# EEZ_CF-DIC_r5B7.net
KiCad netlist of a schematic drawn in EAGLE
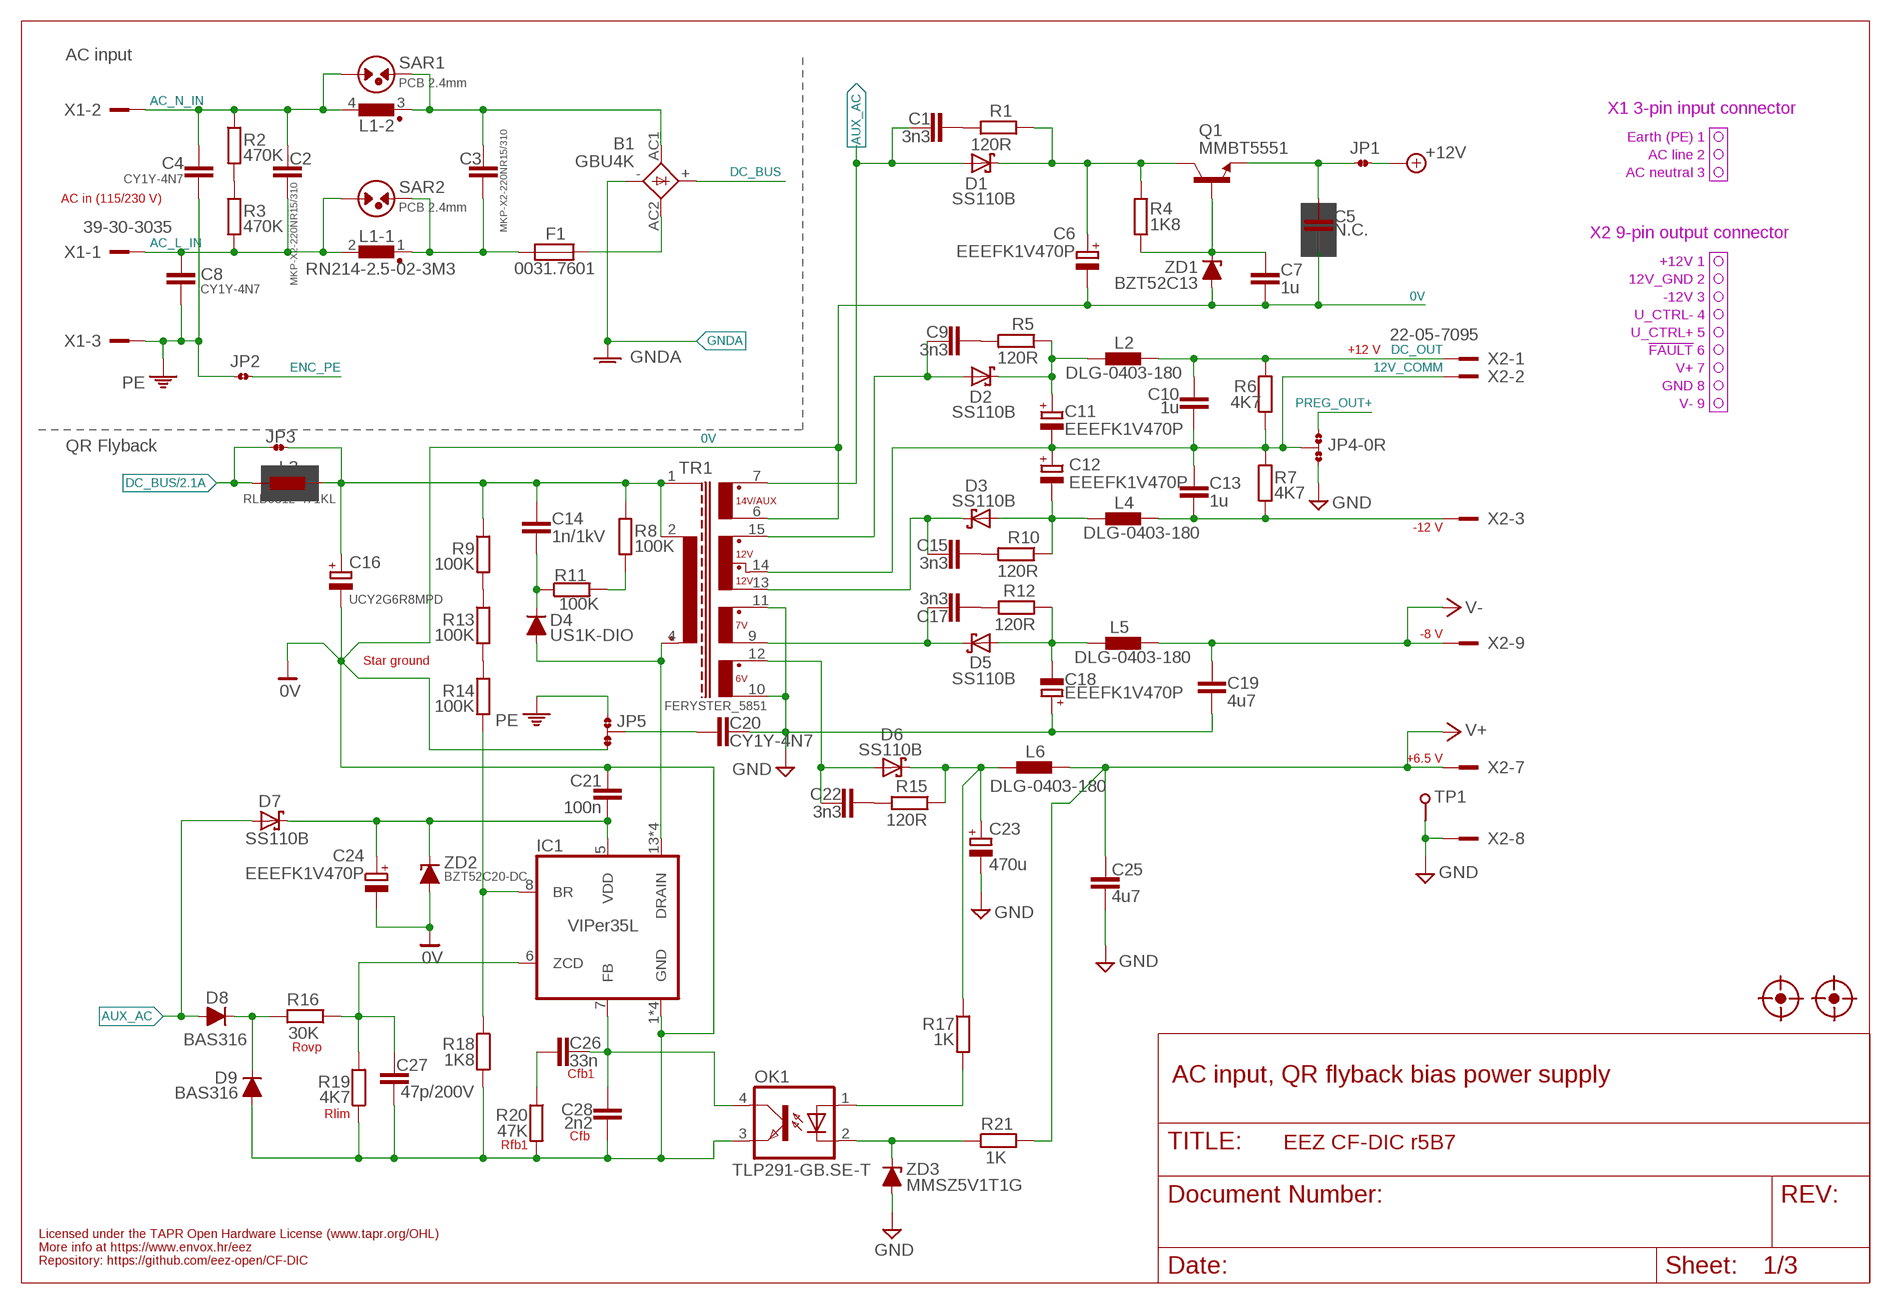
[diagram p0: schematic, sheet 1]
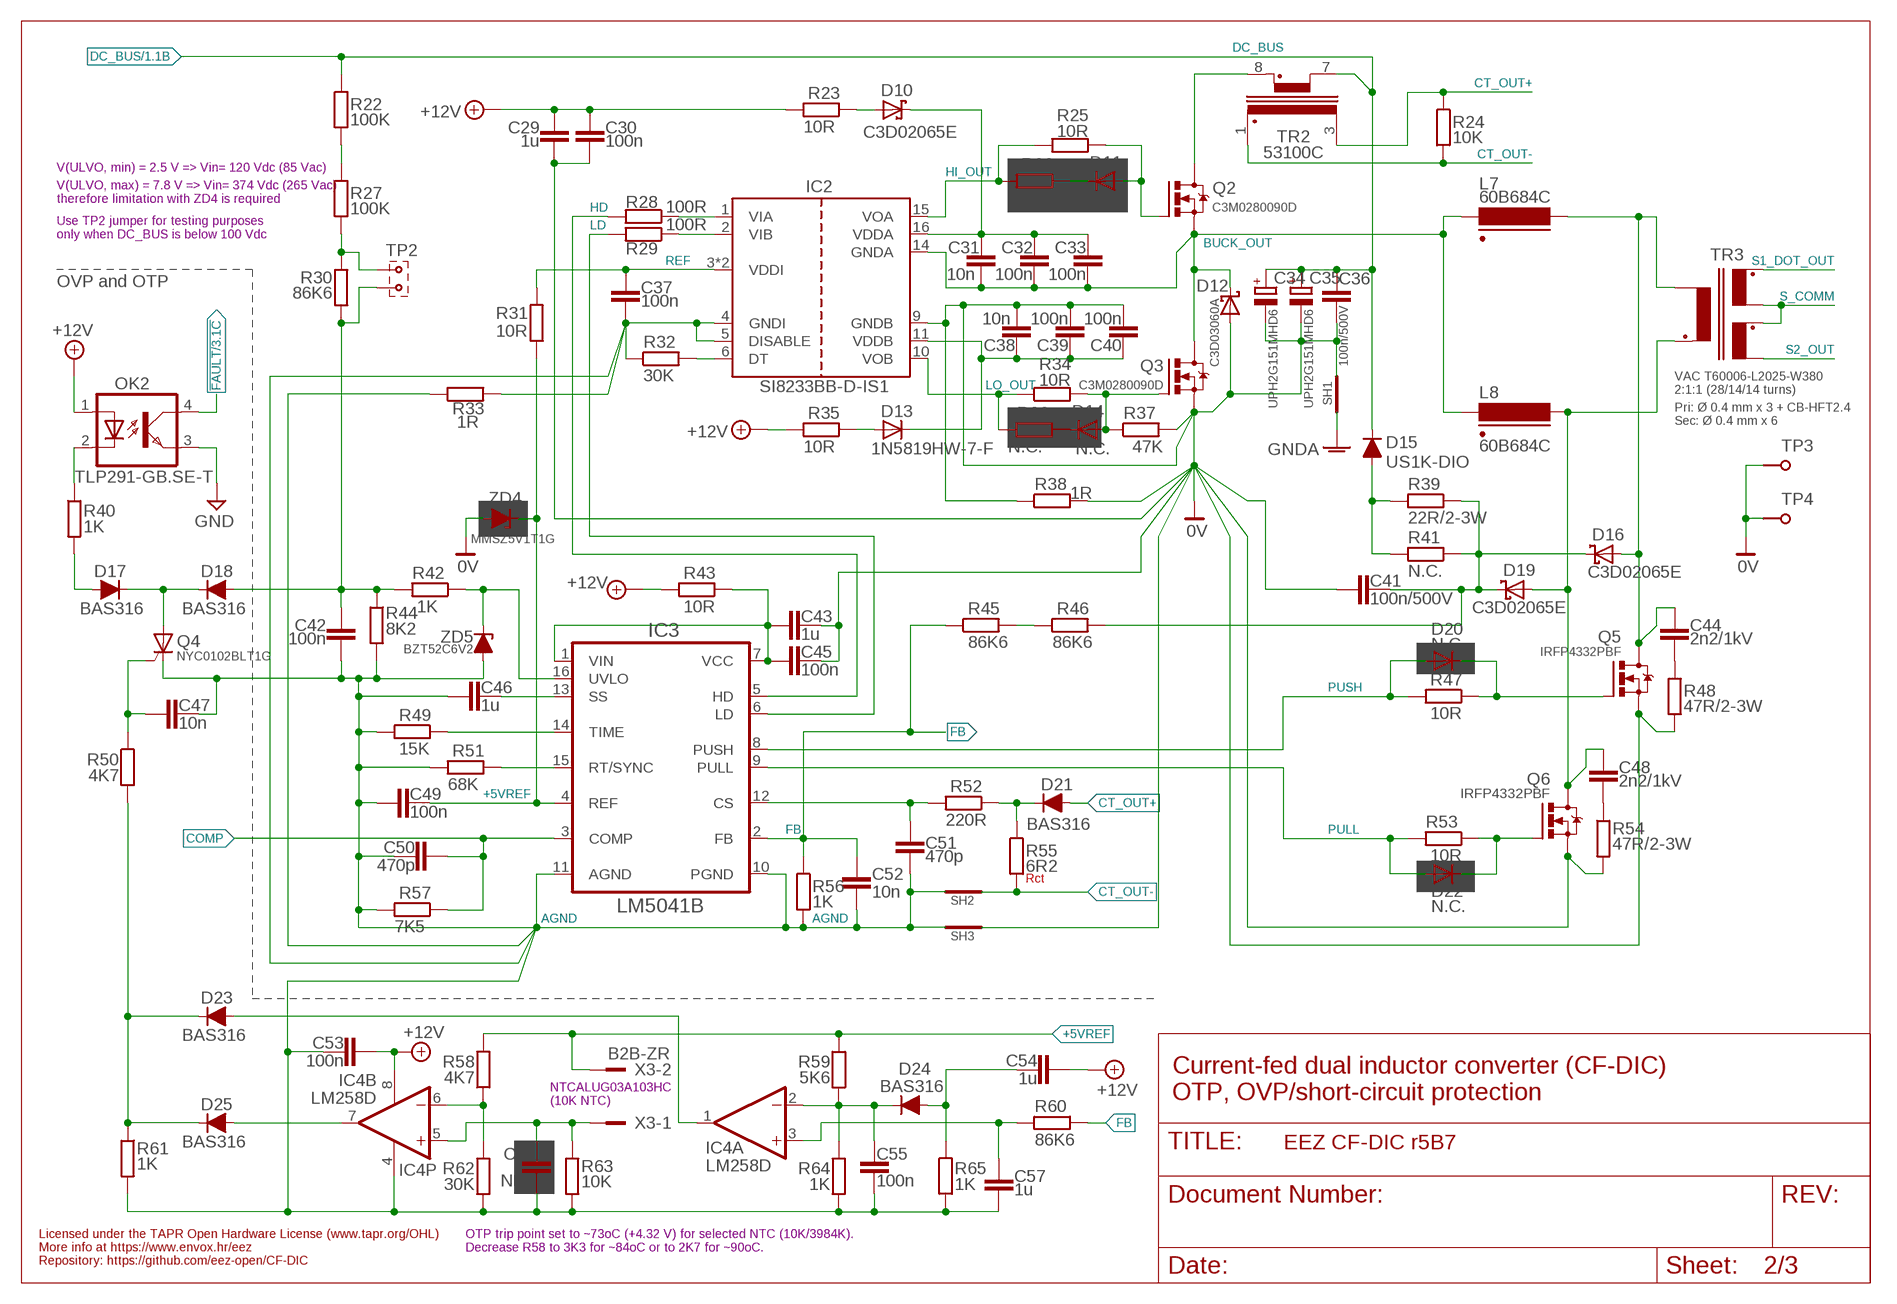
[diagram p1: schematic, sheet 2]
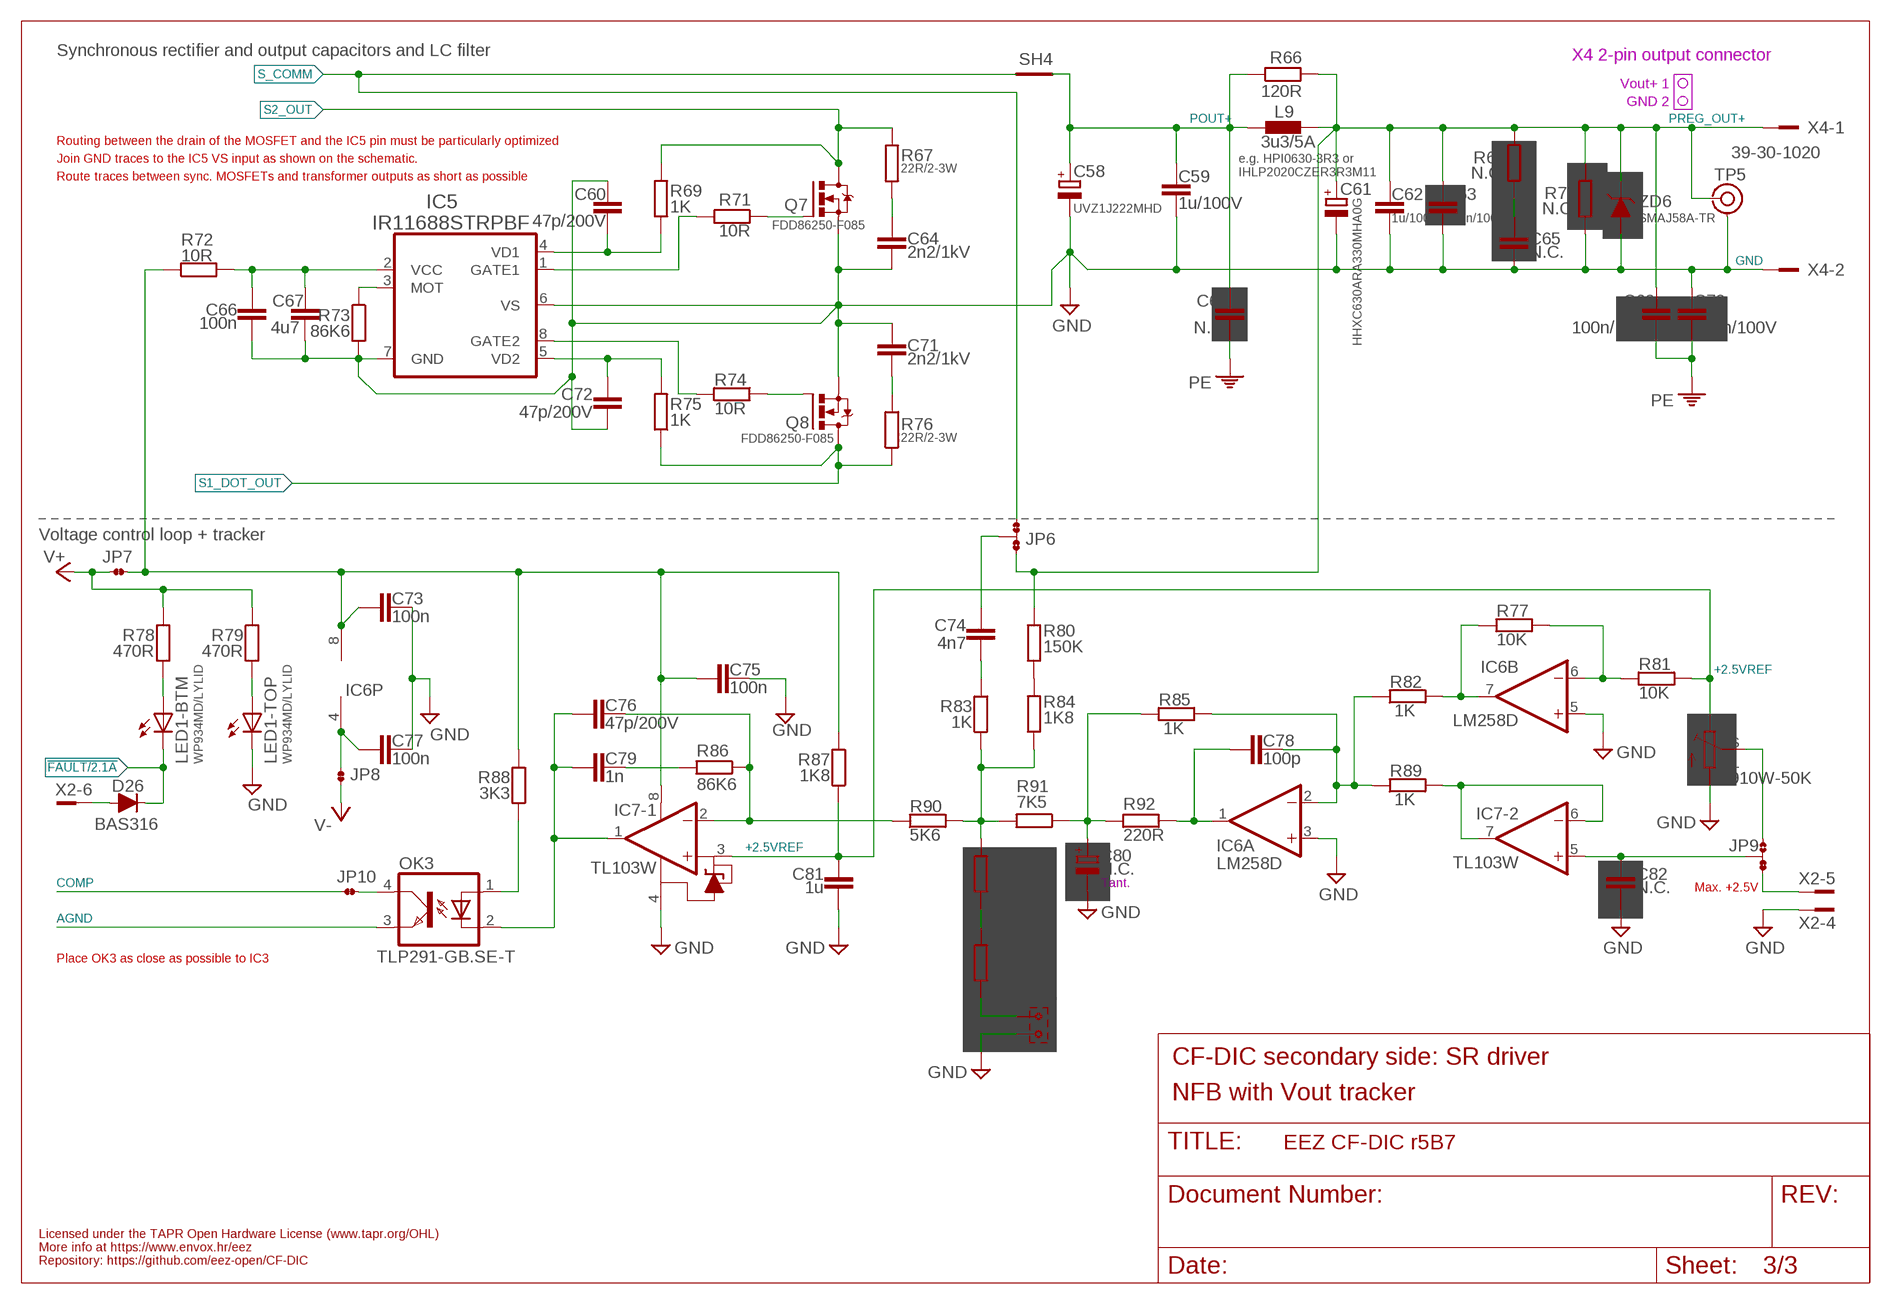
[diagram p2: schematic, sheet 3]

(export (version "E")
  (design (tool "Eeschema 10.0.6"))
  (components
    (comp (ref "C58")
      (value "UVZ1J222MHD")
      (footprint "eagle-import:ECAP7.5_18-H35.5A")
      (libsource (lib "eagle-import") (part "ECAPH35.5A"))
    )
    (comp (ref "C59")
      (value "1u/100V")
      (footprint "eagle-import:C1206")
      (libsource (lib "eagle-import") (part "C-EUC1206"))
    )
    (comp (ref "C60")
      (value "47p/200V")
      (footprint "eagle-import:C0805")
      (libsource (lib "eagle-import") (part "C-EUC0805"))
    )
    (comp (ref "C61")
      (value "HHXC630ARA330MHA0G")
      (footprint "eagle-import:CAPAE830X1050N")
      (libsource (lib "eagle-import") (part "ECAPSMD8.3MM/HA0"))
    )
    (comp (ref "C62")
      (value "1u/100V")
      (footprint "eagle-import:C1206")
      (libsource (lib "eagle-import") (part "C-EUC1206"))
    )
    (comp (ref "C63")
      (value "100n/100V")
      (footprint "eagle-import:C1206")
      (libsource (lib "eagle-import") (part "C-EUC1206"))
    )
    (comp (ref "C64")
      (value "2n2/1kV")
      (footprint "eagle-import:C1210")
      (libsource (lib "eagle-import") (part "C-EUC1210"))
    )
    (comp (ref "C65")
      (value "N.C.")
      (footprint "eagle-import:C1206")
      (libsource (lib "eagle-import") (part "C-EUC1206"))
    )
    (comp (ref "C66")
      (value "100n")
      (footprint "eagle-import:C0603")
      (libsource (lib "eagle-import") (part "C-EUC0603"))
    )
    (comp (ref "C67")
      (value "4u7")
      (footprint "eagle-import:C1206")
      (libsource (lib "eagle-import") (part "C-EUC1206"))
    )
    (comp (ref "C68")
      (value "N.C.")
      (footprint "eagle-import:C1206")
      (libsource (lib "eagle-import") (part "C-EUC1206"))
    )
    (comp (ref "C69")
      (value "100n/100V")
      (footprint "eagle-import:C1206")
      (libsource (lib "eagle-import") (part "C-EUC1206"))
    )
    (comp (ref "C70")
      (value "100n/100V")
      (footprint "eagle-import:C1206")
      (libsource (lib "eagle-import") (part "C-EUC1206"))
    )
    (comp (ref "C71")
      (value "2n2/1kV")
      (footprint "eagle-import:C1210")
      (libsource (lib "eagle-import") (part "C-EUC1210"))
    )
    (comp (ref "C72")
      (value "47p/200V")
      (footprint "eagle-import:C0805")
      (libsource (lib "eagle-import") (part "C-EUC0805"))
    )
    (comp (ref "C73")
      (value "100n")
      (footprint "eagle-import:C0603")
      (libsource (lib "eagle-import") (part "C-EUC0603"))
    )
    (comp (ref "C74")
      (value "4n7")
      (footprint "eagle-import:C0805")
      (libsource (lib "eagle-import") (part "C-EUC0805"))
    )
    (comp (ref "C75")
      (value "100n")
      (footprint "eagle-import:C0603")
      (libsource (lib "eagle-import") (part "C-EUC0603"))
    )
    (comp (ref "C76")
      (value "47p/200V")
      (footprint "eagle-import:C0805")
      (libsource (lib "eagle-import") (part "C-EUC0805"))
    )
    (comp (ref "C77")
      (value "100n")
      (footprint "eagle-import:C0603")
      (libsource (lib "eagle-import") (part "C-EUC0603"))
    )
    (comp (ref "C78")
      (value "100p")
      (footprint "eagle-import:C0805")
      (libsource (lib "eagle-import") (part "C-EUC0805"))
    )
    (comp (ref "C79")
      (value "1n")
      (footprint "eagle-import:C0805")
      (libsource (lib "eagle-import") (part "C-EUC0805"))
    )
    (comp (ref "C80")
      (value "N.C.")
      (footprint "eagle-import:EC1206")
      (libsource (lib "eagle-import") (part "ECAP1206"))
    )
    (comp (ref "C81")
      (value "1u")
      (footprint "eagle-import:C0805")
      (libsource (lib "eagle-import") (part "C-EUC0805"))
    )
    (comp (ref "C82")
      (value "N.C.")
      (footprint "eagle-import:C0805")
      (libsource (lib "eagle-import") (part "C-EUC0805"))
    )
    (comp (ref "D26")
      (value "BAS316")
      (footprint "eagle-import:SOD323-R")
      (libsource (lib "eagle-import") (part "DIODESOD323R"))
    )
    (comp (ref "IC5")
      (value "IR11688STRPBF")
      (footprint "eagle-import:SO8")
      (libsource (lib "eagle-import") (part "IR11688"))
    )
    (comp (ref "IC6")
      (value "LM258D")
      (footprint "eagle-import:SOIC127P600X173-8N")
      (libsource (lib "eagle-import") (part "TL072SOIC8"))
    )
    (comp (ref "IC7")
      (value "TL103W")
      (footprint "eagle-import:SOIC127P600X173-8N")
      (libsource (lib "eagle-import") (part "TL103W"))
    )
    (comp (ref "JP6")
      (value "JP3-CUT")
      (footprint "eagle-import:JP3-CUT")
      (libsource (lib "eagle-import") (part "JP3-CUT"))
    )
    (comp (ref "JP7")
      (value "JP2-NOCUT")
      (footprint "eagle-import:JP2-NOCUT")
      (libsource (lib "eagle-import") (part "JP2-NOCUT"))
    )
    (comp (ref "JP8")
      (value "JP2-NOCUT")
      (footprint "eagle-import:JP2-NOCUT")
      (libsource (lib "eagle-import") (part "JP2-NOCUT"))
    )
    (comp (ref "JP9")
      (value "JP3-CUT")
      (footprint "eagle-import:JP3-CUT")
      (libsource (lib "eagle-import") (part "JP3-CUT"))
    )
    (comp (ref "JP10")
      (value "JP2-NOCUT")
      (footprint "eagle-import:JP2-NOCUT")
      (libsource (lib "eagle-import") (part "JP2-NOCUT"))
    )
    (comp (ref "L9")
      (value "3u3/5A")
      (footprint "eagle-import:COILCRAFT_HPI0630")
      (libsource (lib "eagle-import") (part "COILCRAFT_HPI0630"))
    )
    (comp (ref "LED1")
      (value "WP934MD/LYLID")
      (footprint "eagle-import:WP934MD")
      (libsource (lib "eagle-import") (part "WP934MD/LYLID"))
    )
    (comp (ref "OK3")
      (value "TLP291-GB.SE-T")
      (footprint "eagle-import:SO4")
      (libsource (lib "eagle-import") (part "TLP291"))
    )
    (comp (ref "P1")
      (value "T910W-50K")
      (footprint "eagle-import:S64W")
      (libsource (lib "eagle-import") (part "TPOT-S64W"))
    )
    (comp (ref "Q7")
      (value "FDD86250-F085")
      (footprint "eagle-import:TO229P990X239-3N")
      (libsource (lib "eagle-import") (part "N-MOSFETDPAK"))
    )
    (comp (ref "Q8")
      (value "FDD86250-F085")
      (footprint "eagle-import:TO229P990X239-3N")
      (libsource (lib "eagle-import") (part "N-MOSFETDPAK"))
    )
    (comp (ref "R66")
      (value "120R")
      (footprint "eagle-import:R0805")
      (libsource (lib "eagle-import") (part "R-EU_R0805"))
    )
    (comp (ref "R67")
      (value "22R/2-3W")
      (footprint "eagle-import:R2512")
      (libsource (lib "eagle-import") (part "R-EU_R2512"))
    )
    (comp (ref "R68")
      (value "N.C.")
      (footprint "eagle-import:R1210")
      (libsource (lib "eagle-import") (part "R-EU_R1210"))
    )
    (comp (ref "R69")
      (value "1K")
      (footprint "eagle-import:R0805")
      (libsource (lib "eagle-import") (part "R-EU_R0805"))
    )
    (comp (ref "R70")
      (value "N.C.")
      (footprint "eagle-import:R2512")
      (libsource (lib "eagle-import") (part "R-EU_R2512"))
    )
    (comp (ref "R71")
      (value "10R")
      (footprint "eagle-import:R0805")
      (libsource (lib "eagle-import") (part "R-EU_R0805"))
    )
    (comp (ref "R72")
      (value "10R")
      (footprint "eagle-import:R0805")
      (libsource (lib "eagle-import") (part "R-EU_R0805"))
    )
    (comp (ref "R73")
      (value "86K6")
      (footprint "eagle-import:R0805")
      (libsource (lib "eagle-import") (part "R-EU_R0805"))
    )
    (comp (ref "R74")
      (value "10R")
      (footprint "eagle-import:R0805")
      (libsource (lib "eagle-import") (part "R-EU_R0805"))
    )
    (comp (ref "R75")
      (value "1K")
      (footprint "eagle-import:R0805")
      (libsource (lib "eagle-import") (part "R-EU_R0805"))
    )
    (comp (ref "R76")
      (value "22R/2-3W")
      (footprint "eagle-import:R2512")
      (libsource (lib "eagle-import") (part "R-EU_R2512"))
    )
    (comp (ref "R77")
      (value "10K")
      (footprint "eagle-import:R0805")
      (libsource (lib "eagle-import") (part "R-EU_R0805"))
    )
    (comp (ref "R78")
      (value "470R")
      (footprint "eagle-import:R0805")
      (libsource (lib "eagle-import") (part "R-EU_R0805"))
    )
    (comp (ref "R79")
      (value "470R")
      (footprint "eagle-import:R0805")
      (libsource (lib "eagle-import") (part "R-EU_R0805"))
    )
    (comp (ref "R80")
      (value "150K")
      (footprint "eagle-import:R0805")
      (libsource (lib "eagle-import") (part "R-EU_R0805"))
    )
    (comp (ref "R81")
      (value "10K")
      (footprint "eagle-import:R0805")
      (libsource (lib "eagle-import") (part "R-EU_R0805"))
    )
    (comp (ref "R82")
      (value "1K")
      (footprint "eagle-import:R0805")
      (libsource (lib "eagle-import") (part "R-EU_R0805"))
    )
    (comp (ref "R83")
      (value "1K")
      (footprint "eagle-import:R0805")
      (libsource (lib "eagle-import") (part "R-EU_R0805"))
    )
    (comp (ref "R84")
      (value "1K8")
      (footprint "eagle-import:R0805")
      (libsource (lib "eagle-import") (part "R-EU_R0805"))
    )
    (comp (ref "R85")
      (value "1K")
      (footprint "eagle-import:R0805")
      (libsource (lib "eagle-import") (part "R-EU_R0805"))
    )
    (comp (ref "R86")
      (value "86K6")
      (footprint "eagle-import:R0805")
      (libsource (lib "eagle-import") (part "R-EU_R0805"))
    )
    (comp (ref "R87")
      (value "1K8")
      (footprint "eagle-import:R0805")
      (libsource (lib "eagle-import") (part "R-EU_R0805"))
    )
    (comp (ref "R88")
      (value "3K3")
      (footprint "eagle-import:R0805")
      (libsource (lib "eagle-import") (part "R-EU_R0805"))
    )
    (comp (ref "R89")
      (value "1K")
      (footprint "eagle-import:R0805")
      (libsource (lib "eagle-import") (part "R-EU_R0805"))
    )
    (comp (ref "R90")
      (value "5K6")
      (footprint "eagle-import:R0805")
      (libsource (lib "eagle-import") (part "R-EU_R0805"))
    )
    (comp (ref "R91")
      (value "7K5")
      (footprint "eagle-import:R0805")
      (libsource (lib "eagle-import") (part "R-EU_R0805"))
    )
    (comp (ref "R92")
      (value "220R")
      (footprint "eagle-import:R0805")
      (libsource (lib "eagle-import") (part "R-EU_R0805"))
    )
    (comp (ref "R93")
      (value "N.C.")
      (footprint "eagle-import:R0805")
      (libsource (lib "eagle-import") (part "R-EU_R0805"))
    )
    (comp (ref "R94")
      (value "N.C.")
      (footprint "eagle-import:R0805")
      (libsource (lib "eagle-import") (part "R-EU_R0805"))
    )
    (comp (ref "SH4")
      (value "SHORTNOHOLE")
      (footprint "eagle-import:SHORT_NOHOLE")
      (libsource (lib "eagle-import") (part "SHORTNOHOLE"))
    )
    (comp (ref "TP5")
      (value "TEST_POINT-2")
      (footprint "eagle-import:TP_1.1MM_2")
      (libsource (lib "eagle-import") (part "TEST_POINT-2"))
    )
    (comp (ref "TP6")
      (value "JUMPER-2PIN-2MM")
      (footprint "eagle-import:2MM-2")
      (libsource (lib "eagle-import") (part "JUMPER-2PIN-2MM"))
    )
    (comp (ref "X2")
      (value "22-05-7095")
      (footprint "eagle-import:SPOX_22-05-7095")
      (libsource (lib "eagle-import") (part "SPOX_22-05-7095"))
    )
    (comp (ref "X4")
      (value "39-30-1020")
      (footprint "eagle-import:MINIFIT_39301020")
      (libsource (lib "eagle-import") (part "MINIFIT_39301020"))
    )
    (comp (ref "ZD6")
      (value "SMAJ58A-TR")
      (footprint "eagle-import:DO214AC")
      (libsource (lib "eagle-import") (part "PSMAXX"))
    )
    (comp (ref "C29")
      (value "1u")
      (footprint "eagle-import:C0805")
      (libsource (lib "eagle-import") (part "C-EUC0805"))
    )
    (comp (ref "C30")
      (value "100n")
      (footprint "eagle-import:C0603")
      (libsource (lib "eagle-import") (part "C-EUC0603"))
    )
    (comp (ref "C31")
      (value "10n")
      (footprint "eagle-import:C0603")
      (libsource (lib "eagle-import") (part "C-EUC0603"))
    )
    (comp (ref "C32")
      (value "100n")
      (footprint "eagle-import:C0603")
      (libsource (lib "eagle-import") (part "C-EUC0603"))
    )
    (comp (ref "C33")
      (value "100n")
      (footprint "eagle-import:C0603")
      (libsource (lib "eagle-import") (part "C-EUC0603"))
    )
    (comp (ref "C34")
      (value "UPH2G151MHD6")
      (footprint "eagle-import:ECAP7.5_18")
      (libsource (lib "eagle-import") (part "ECAP7.5G_18MM"))
    )
    (comp (ref "C35")
      (value "UPH2G151MHD6")
      (footprint "eagle-import:ECAP7.5_18")
      (libsource (lib "eagle-import") (part "ECAP7.5G_18MM"))
    )
    (comp (ref "C36")
      (value "100n/500V")
      (footprint "eagle-import:C1812")
      (libsource (lib "eagle-import") (part "C-EUC1812"))
    )
    (comp (ref "C37")
      (value "100n")
      (footprint "eagle-import:C0603")
      (libsource (lib "eagle-import") (part "C-EUC0603"))
    )
    (comp (ref "C38")
      (value "10n")
      (footprint "eagle-import:C0603")
      (libsource (lib "eagle-import") (part "C-EUC0603"))
    )
    (comp (ref "C39")
      (value "100n")
      (footprint "eagle-import:C0603")
      (libsource (lib "eagle-import") (part "C-EUC0603"))
    )
    (comp (ref "C40")
      (value "100n")
      (footprint "eagle-import:C0603")
      (libsource (lib "eagle-import") (part "C-EUC0603"))
    )
    (comp (ref "C41")
      (value "100n/500V")
      (footprint "eagle-import:C1812")
      (libsource (lib "eagle-import") (part "C-EUC1812"))
    )
    (comp (ref "C42")
      (value "100n")
      (footprint "eagle-import:C0603")
      (libsource (lib "eagle-import") (part "C-EUC0603"))
    )
    (comp (ref "C43")
      (value "1u")
      (footprint "eagle-import:C0805")
      (libsource (lib "eagle-import") (part "C-EUC0805"))
    )
    (comp (ref "C44")
      (value "2n2/1kV")
      (footprint "eagle-import:C1210")
      (libsource (lib "eagle-import") (part "C-EUC1210"))
    )
    (comp (ref "C45")
      (value "100n")
      (footprint "eagle-import:C0603")
      (libsource (lib "eagle-import") (part "C-EUC0603"))
    )
    (comp (ref "C46")
      (value "1u")
      (footprint "eagle-import:C0805")
      (libsource (lib "eagle-import") (part "C-EUC0805"))
    )
    (comp (ref "C47")
      (value "10n")
      (footprint "eagle-import:C0603")
      (libsource (lib "eagle-import") (part "C-EUC0603"))
    )
    (comp (ref "C48")
      (value "2n2/1kV")
      (footprint "eagle-import:C1210")
      (libsource (lib "eagle-import") (part "C-EUC1210"))
    )
    (comp (ref "C49")
      (value "100n")
      (footprint "eagle-import:C0603")
      (libsource (lib "eagle-import") (part "C-EUC0603"))
    )
    (comp (ref "C50")
      (value "470p")
      (footprint "eagle-import:C0805")
      (libsource (lib "eagle-import") (part "C-EUC0805"))
    )
    (comp (ref "C51")
      (value "470p")
      (footprint "eagle-import:C0805")
      (libsource (lib "eagle-import") (part "C-EUC0805"))
    )
    (comp (ref "C52")
      (value "10n")
      (footprint "eagle-import:C0603")
      (libsource (lib "eagle-import") (part "C-EUC0603"))
    )
    (comp (ref "C53")
      (value "100n")
      (footprint "eagle-import:C0603")
      (libsource (lib "eagle-import") (part "C-EUC0603"))
    )
    (comp (ref "C54")
      (value "1u")
      (footprint "eagle-import:C0805")
      (libsource (lib "eagle-import") (part "C-EUC0805"))
    )
    (comp (ref "C55")
      (value "100n")
      (footprint "eagle-import:C0603")
      (libsource (lib "eagle-import") (part "C-EUC0603"))
    )
    (comp (ref "C56")
      (value "N.C.")
      (footprint "eagle-import:C0603")
      (libsource (lib "eagle-import") (part "C-EUC0603"))
    )
    (comp (ref "C57")
      (value "1u")
      (footprint "eagle-import:C0805")
      (libsource (lib "eagle-import") (part "C-EUC0805"))
    )
    (comp (ref "D10")
      (value "C3D02065E")
      (footprint "eagle-import:TO252-L")
      (libsource (lib "eagle-import") (part "SCHOTTKY-SIC_L"))
    )
    (comp (ref "D11")
      (value "N.C.")
      (footprint "eagle-import:SOD323-W")
      (libsource (lib "eagle-import") (part "DIODE-SOD323-W"))
    )
    (comp (ref "D12")
      (value "C3D03060A")
      (footprint "eagle-import:TO220-2")
      (libsource (lib "eagle-import") (part "SCHOTTKY-TO220"))
    )
    (comp (ref "D13")
      (value "1N5819HW-7-F")
      (footprint "eagle-import:SOD323-W")
      (libsource (lib "eagle-import") (part "DIODE-SOD323-W"))
    )
    (comp (ref "D14")
      (value "N.C.")
      (footprint "eagle-import:SOD323-W")
      (libsource (lib "eagle-import") (part "DIODE-SOD323-W"))
    )
    (comp (ref "D15")
      (value "US1K-DIO")
      (footprint "eagle-import:DO214AA")
      (libsource (lib "eagle-import") (part "DIODEDO214AA"))
    )
    (comp (ref "D16")
      (value "C3D02065E")
      (footprint "eagle-import:TO252-L")
      (libsource (lib "eagle-import") (part "SCHOTTKY-SIC_L"))
    )
    (comp (ref "D17")
      (value "BAS316")
      (footprint "eagle-import:SOD323-R")
      (libsource (lib "eagle-import") (part "DIODESOD323R"))
    )
    (comp (ref "D18")
      (value "BAS316")
      (footprint "eagle-import:SOD323-R")
      (libsource (lib "eagle-import") (part "DIODESOD323R"))
    )
    (comp (ref "D19")
      (value "C3D02065E")
      (footprint "eagle-import:TO252-L")
      (libsource (lib "eagle-import") (part "SCHOTTKY-SIC_L"))
    )
    (comp (ref "D20")
      (value "N.C.")
      (footprint "eagle-import:SOD323-W")
      (libsource (lib "eagle-import") (part "DIODE-SOD323-W"))
    )
    (comp (ref "D21")
      (value "BAS316")
      (footprint "eagle-import:SOD323-R")
      (libsource (lib "eagle-import") (part "DIODESOD323R"))
    )
    (comp (ref "D22")
      (value "N.C.")
      (footprint "eagle-import:SOD323-W")
      (libsource (lib "eagle-import") (part "DIODE-SOD323-W"))
    )
    (comp (ref "D23")
      (value "BAS316")
      (footprint "eagle-import:SOD323-R")
      (libsource (lib "eagle-import") (part "DIODESOD323R"))
    )
    (comp (ref "D24")
      (value "BAS316")
      (footprint "eagle-import:SOD323-R")
      (libsource (lib "eagle-import") (part "DIODESOD323R"))
    )
    (comp (ref "D25")
      (value "BAS316")
      (footprint "eagle-import:SOD323-R")
      (libsource (lib "eagle-import") (part "DIODESOD323R"))
    )
    (comp (ref "IC2")
      (value "SI8233BB-D-IS1")
      (footprint "eagle-import:SOIC-16")
      (libsource (lib "eagle-import") (part "SI8233"))
    )
    (comp (ref "IC3")
      (value "LM5041B")
      (footprint "eagle-import:MTC16")
      (fields (field (name "MANUFACTURER_PART_NUMBER") "lm5041mtcnopb"))
      (libsource (lib "eagle-import") (part "LM5041"))
    )
    (comp (ref "IC4")
      (value "LM258D")
      (footprint "eagle-import:SOIC127P600X173-8N")
      (libsource (lib "eagle-import") (part "TL072SOIC8"))
    )
    (comp (ref "L7")
      (value "60B684C")
      (footprint "eagle-import:MURATA_6000B")
      (libsource (lib "eagle-import") (part "MURATA_6000B"))
    )
    (comp (ref "L8")
      (value "60B684C")
      (footprint "eagle-import:MURATA_6000B")
      (libsource (lib "eagle-import") (part "MURATA_6000B"))
    )
    (comp (ref "OK2")
      (value "TLP291-GB.SE-T")
      (footprint "eagle-import:SO4")
      (libsource (lib "eagle-import") (part "TLP291"))
    )
    (comp (ref "Q2")
      (value "C3M0280090D")
      (footprint "eagle-import:TO247BV")
      (libsource (lib "eagle-import") (part "IRFP240"))
    )
    (comp (ref "Q3")
      (value "C3M0280090D")
      (footprint "eagle-import:TO247BV")
      (libsource (lib "eagle-import") (part "IRFP240"))
    )
    (comp (ref "Q4")
      (value "NYC0102BLT1G")
      (footprint "eagle-import:SOT23")
      (libsource (lib "eagle-import") (part "NYC0102BLT1G"))
    )
    (comp (ref "Q5")
      (value "IRFP4332PBF")
      (footprint "eagle-import:TO247BV")
      (libsource (lib "eagle-import") (part "IRFP240"))
    )
    (comp (ref "Q6")
      (value "IRFP4332PBF")
      (footprint "eagle-import:TO247BV")
      (libsource (lib "eagle-import") (part "IRFP240"))
    )
    (comp (ref "R22")
      (value "100K")
      (footprint "eagle-import:R1206")
      (libsource (lib "eagle-import") (part "R-EU_R1206"))
    )
    (comp (ref "R23")
      (value "10R")
      (footprint "eagle-import:R0805")
      (libsource (lib "eagle-import") (part "R-EU_R0805"))
    )
    (comp (ref "R24")
      (value "10K")
      (footprint "eagle-import:R0805")
      (libsource (lib "eagle-import") (part "R-EU_R0805"))
    )
    (comp (ref "R25")
      (value "10R")
      (footprint "eagle-import:R0805")
      (libsource (lib "eagle-import") (part "R-EU_R0805"))
    )
    (comp (ref "R26")
      (value "N.C.")
      (footprint "eagle-import:R0805")
      (libsource (lib "eagle-import") (part "R-EU_R0805"))
    )
    (comp (ref "R27")
      (value "100K")
      (footprint "eagle-import:R1206")
      (libsource (lib "eagle-import") (part "R-EU_R1206"))
    )
    (comp (ref "R28")
      (value "100R")
      (footprint "eagle-import:R0805")
      (libsource (lib "eagle-import") (part "R-EU_R0805"))
    )
    (comp (ref "R29")
      (value "100R")
      (footprint "eagle-import:R0805")
      (libsource (lib "eagle-import") (part "R-EU_R0805"))
    )
    (comp (ref "R30")
      (value "86K6")
      (footprint "eagle-import:R0805")
      (libsource (lib "eagle-import") (part "R-EU_R0805"))
    )
    (comp (ref "R31")
      (value "10R")
      (footprint "eagle-import:R0805")
      (libsource (lib "eagle-import") (part "R-EU_R0805"))
    )
    (comp (ref "R32")
      (value "30K")
      (footprint "eagle-import:R0805")
      (libsource (lib "eagle-import") (part "R-EU_R0805"))
    )
    (comp (ref "R33")
      (value "1R")
      (footprint "eagle-import:R0805")
      (libsource (lib "eagle-import") (part "R-EU_R0805"))
    )
    (comp (ref "R34")
      (value "10R")
      (footprint "eagle-import:R0805")
      (libsource (lib "eagle-import") (part "R-EU_R0805"))
    )
    (comp (ref "R35")
      (value "10R")
      (footprint "eagle-import:R0805")
      (libsource (lib "eagle-import") (part "R-EU_R0805"))
    )
    (comp (ref "R36")
      (value "N.C.")
      (footprint "eagle-import:R0805")
      (libsource (lib "eagle-import") (part "R-EU_R0805"))
    )
    (comp (ref "R37")
      (value "47K")
      (footprint "eagle-import:R0805")
      (libsource (lib "eagle-import") (part "R-EU_R0805"))
    )
    (comp (ref "R38")
      (value "1R")
      (footprint "eagle-import:R0805")
      (libsource (lib "eagle-import") (part "R-EU_R0805"))
    )
    (comp (ref "R39")
      (value "22R/2-3W")
      (footprint "eagle-import:R2512")
      (libsource (lib "eagle-import") (part "R-EU_R2512"))
    )
    (comp (ref "R40")
      (value "1K")
      (footprint "eagle-import:R0805")
      (libsource (lib "eagle-import") (part "R-EU_R0805"))
    )
    (comp (ref "R41")
      (value "N.C.")
      (footprint "eagle-import:R2512")
      (libsource (lib "eagle-import") (part "R-EU_R2512"))
    )
    (comp (ref "R42")
      (value "1K")
      (footprint "eagle-import:R0805")
      (libsource (lib "eagle-import") (part "R-EU_R0805"))
    )
    (comp (ref "R43")
      (value "10R")
      (footprint "eagle-import:R0805")
      (libsource (lib "eagle-import") (part "R-EU_R0805"))
    )
    (comp (ref "R44")
      (value "8K2")
      (footprint "eagle-import:R0805")
      (libsource (lib "eagle-import") (part "R-EU_R0805"))
    )
    (comp (ref "R45")
      (value "86K6")
      (footprint "eagle-import:R0805")
      (libsource (lib "eagle-import") (part "R-EU_R0805"))
    )
    (comp (ref "R46")
      (value "86K6")
      (footprint "eagle-import:R0805")
      (libsource (lib "eagle-import") (part "R-EU_R0805"))
    )
    (comp (ref "R47")
      (value "10R")
      (footprint "eagle-import:R0805")
      (libsource (lib "eagle-import") (part "R-EU_R0805"))
    )
    (comp (ref "R48")
      (value "47R/2-3W")
      (footprint "eagle-import:R2512")
      (libsource (lib "eagle-import") (part "R-EU_R2512"))
    )
    (comp (ref "R49")
      (value "15K")
      (footprint "eagle-import:R0805")
      (libsource (lib "eagle-import") (part "R-EU_R0805"))
    )
    (comp (ref "R50")
      (value "4K7")
      (footprint "eagle-import:R0805")
      (libsource (lib "eagle-import") (part "R-EU_R0805"))
    )
    (comp (ref "R51")
      (value "68K")
      (footprint "eagle-import:R0805")
      (libsource (lib "eagle-import") (part "R-EU_R0805"))
    )
    (comp (ref "R52")
      (value "220R")
      (footprint "eagle-import:R0805")
      (libsource (lib "eagle-import") (part "R-EU_R0805"))
    )
    (comp (ref "R53")
      (value "10R")
      (footprint "eagle-import:R0805")
      (libsource (lib "eagle-import") (part "R-EU_R0805"))
    )
    (comp (ref "R54")
      (value "47R/2-3W")
      (footprint "eagle-import:R2512")
      (libsource (lib "eagle-import") (part "R-EU_R2512"))
    )
    (comp (ref "R55")
      (value "6R2")
      (footprint "eagle-import:R0805")
      (libsource (lib "eagle-import") (part "R-EU_R0805"))
    )
    (comp (ref "R56")
      (value "1K")
      (footprint "eagle-import:R0805")
      (libsource (lib "eagle-import") (part "R-EU_R0805"))
    )
    (comp (ref "R57")
      (value "7K5")
      (footprint "eagle-import:R0805")
      (libsource (lib "eagle-import") (part "R-EU_R0805"))
    )
    (comp (ref "R58")
      (value "4K7")
      (footprint "eagle-import:R0805")
      (libsource (lib "eagle-import") (part "R-EU_R0805"))
    )
    (comp (ref "R59")
      (value "5K6")
      (footprint "eagle-import:R0805")
      (libsource (lib "eagle-import") (part "R-EU_R0805"))
    )
    (comp (ref "R60")
      (value "86K6")
      (footprint "eagle-import:R0805")
      (libsource (lib "eagle-import") (part "R-EU_R0805"))
    )
    (comp (ref "R61")
      (value "1K")
      (footprint "eagle-import:R0805")
      (libsource (lib "eagle-import") (part "R-EU_R0805"))
    )
    (comp (ref "R62")
      (value "30K")
      (footprint "eagle-import:R0805")
      (libsource (lib "eagle-import") (part "R-EU_R0805"))
    )
    (comp (ref "R63")
      (value "10K")
      (footprint "eagle-import:R0805")
      (libsource (lib "eagle-import") (part "R-EU_R0805"))
    )
    (comp (ref "R64")
      (value "1K")
      (footprint "eagle-import:R0805")
      (libsource (lib "eagle-import") (part "R-EU_R0805"))
    )
    (comp (ref "R65")
      (value "1K")
      (footprint "eagle-import:R0805")
      (libsource (lib "eagle-import") (part "R-EU_R0805"))
    )
    (comp (ref "SH1")
      (value "SHORTNOHOLE")
      (footprint "eagle-import:SHORT_NOHOLE")
      (libsource (lib "eagle-import") (part "SHORTNOHOLE"))
    )
    (comp (ref "SH2")
      (value "SHORTNOHOLE")
      (footprint "eagle-import:SHORT_NOHOLE")
      (libsource (lib "eagle-import") (part "SHORTNOHOLE"))
    )
    (comp (ref "SH3")
      (value "SHORTNOHOLE")
      (footprint "eagle-import:SHORT_NOHOLE")
      (libsource (lib "eagle-import") (part "SHORTNOHOLE"))
    )
    (comp (ref "TP2")
      (value "JUMPER-2PIN-2MM")
      (footprint "eagle-import:2MM-2")
      (libsource (lib "eagle-import") (part "JUMPER-2PIN-2MM"))
    )
    (comp (ref "TP3")
      (value "TEST-PIN1.2")
      (footprint "eagle-import:TEST-PIN_1.2MM")
      (libsource (lib "eagle-import") (part "TEST-PIN1.2"))
    )
    (comp (ref "TP4")
      (value "TEST-PIN1.2")
      (footprint "eagle-import:TEST-PIN_1.2MM")
      (libsource (lib "eagle-import") (part "TEST-PIN1.2"))
    )
    (comp (ref "TR2")
      (value "53100C")
      (footprint "eagle-import:MURATA_5300")
      (libsource (lib "eagle-import") (part "MURATA_5300"))
    )
    (comp (ref "TR3")
      (value "VAC T60006-L2025-W380")
      (footprint "eagle-import:VAC_DUAL_SEC")
      (libsource (lib "eagle-import") (part "PCB_TRAFO_FLYBACK2-VAC"))
    )
    (comp (ref "X3")
      (value "B2B-ZR")
      (footprint "eagle-import:B2B-ZR")
      (libsource (lib "eagle-import") (part "B2B-ZR"))
    )
    (comp (ref "ZD4")
      (value "MMSZ5V1T1G")
      (footprint "eagle-import:SOD123")
      (libsource (lib "eagle-import") (part "ZENER-DIODESOD123"))
    )
    (comp (ref "ZD5")
      (value "BZT52C6V2")
      (footprint "eagle-import:SOD123")
      (libsource (lib "eagle-import") (part "ZENER-DIODESOD123"))
    )
    (comp (ref "B1")
      (value "GBU4K")
      (footprint "eagle-import:GBU4K_CRE")
      (libsource (lib "eagle-import") (part "BRIDGE-CREEPAGE"))
    )
    (comp (ref "C1")
      (value "3n3")
      (footprint "eagle-import:C0805")
      (libsource (lib "eagle-import") (part "C-EUC0805"))
    )
    (comp (ref "C2")
      (value "MKP-X2-220NR15/310")
      (footprint "eagle-import:C150-072X183")
      (libsource (lib "eagle-import") (part "C-EU150-072X183"))
    )
    (comp (ref "C3")
      (value "MKP-X2-220NR15/310")
      (footprint "eagle-import:C150-072X183")
      (libsource (lib "eagle-import") (part "C-EU150-072X183"))
    )
    (comp (ref "C4")
      (value "CY1Y-4N7")
      (footprint "eagle-import:CY075-032X103")
      (libsource (lib "eagle-import") (part "C-EUCY"))
    )
    (comp (ref "C5")
      (value "N.C.")
      (footprint "eagle-import:C0603")
      (libsource (lib "eagle-import") (part "C-EUC0603"))
    )
    (comp (ref "C6")
      (value "EEEFK1V470P")
      (footprint "eagle-import:CAPAE660X610N")
      (libsource (lib "eagle-import") (part "ECAPPANASONIC_H"))
    )
    (comp (ref "C7")
      (value "1u")
      (footprint "eagle-import:C0805")
      (libsource (lib "eagle-import") (part "C-EUC0805"))
    )
    (comp (ref "C8")
      (value "CY1Y-4N7")
      (footprint "eagle-import:CY075-032X103")
      (libsource (lib "eagle-import") (part "C-EUCY"))
    )
    (comp (ref "C9")
      (value "3n3")
      (footprint "eagle-import:C0805")
      (libsource (lib "eagle-import") (part "C-EUC0805"))
    )
    (comp (ref "C10")
      (value "1u")
      (footprint "eagle-import:C0805")
      (libsource (lib "eagle-import") (part "C-EUC0805"))
    )
    (comp (ref "C11")
      (value "EEEFK1V470P")
      (footprint "eagle-import:CAPAE660X610N")
      (libsource (lib "eagle-import") (part "ECAPPANASONIC_H"))
    )
    (comp (ref "C12")
      (value "EEEFK1V470P")
      (footprint "eagle-import:CAPAE660X610N")
      (libsource (lib "eagle-import") (part "ECAPPANASONIC_H"))
    )
    (comp (ref "C13")
      (value "1u")
      (footprint "eagle-import:C0805")
      (libsource (lib "eagle-import") (part "C-EUC0805"))
    )
    (comp (ref "C14")
      (value "1n/1kV")
      (footprint "eagle-import:C1210")
      (libsource (lib "eagle-import") (part "C-EUC1210"))
    )
    (comp (ref "C15")
      (value "3n3")
      (footprint "eagle-import:C0805")
      (libsource (lib "eagle-import") (part "C-EUC0805"))
    )
    (comp (ref "C16")
      (value "UCY2G6R8MPD")
      (footprint "eagle-import:ECAP5_10.5")
      (libsource (lib "eagle-import") (part "ECAP5G_10.5MM"))
    )
    (comp (ref "C17")
      (value "3n3")
      (footprint "eagle-import:C0805")
      (libsource (lib "eagle-import") (part "C-EUC0805"))
    )
    (comp (ref "C18")
      (value "EEEFK1V470P")
      (footprint "eagle-import:CAPAE660X610N")
      (libsource (lib "eagle-import") (part "ECAPPANASONIC_H"))
    )
    (comp (ref "C19")
      (value "4u7")
      (footprint "eagle-import:C1206")
      (libsource (lib "eagle-import") (part "C-EUC1206"))
    )
    (comp (ref "C20")
      (value "CY1Y-4N7")
      (footprint "eagle-import:CY075-032X103")
      (libsource (lib "eagle-import") (part "C-EUCY"))
    )
    (comp (ref "C21")
      (value "100n")
      (footprint "eagle-import:C0603")
      (libsource (lib "eagle-import") (part "C-EUC0603"))
    )
    (comp (ref "C22")
      (value "3n3")
      (footprint "eagle-import:C0805")
      (libsource (lib "eagle-import") (part "C-EUC0805"))
    )
    (comp (ref "C23")
      (value "470u")
      (footprint "eagle-import:ECAP5_10.5")
      (libsource (lib "eagle-import") (part "ECAP5G_10.5MM"))
    )
    (comp (ref "C24")
      (value "EEEFK1V470P")
      (footprint "eagle-import:CAPAE660X610N")
      (libsource (lib "eagle-import") (part "ECAPPANASONIC_H"))
    )
    (comp (ref "C25")
      (value "4u7")
      (footprint "eagle-import:C1206")
      (libsource (lib "eagle-import") (part "C-EUC1206"))
    )
    (comp (ref "C26")
      (value "33n")
      (footprint "eagle-import:C0805")
      (libsource (lib "eagle-import") (part "C-EUC0805"))
    )
    (comp (ref "C27")
      (value "47p/200V")
      (footprint "eagle-import:C0805")
      (libsource (lib "eagle-import") (part "C-EUC0805"))
    )
    (comp (ref "C28")
      (value "2n2")
      (footprint "eagle-import:C0805")
      (libsource (lib "eagle-import") (part "C-EUC0805"))
    )
    (comp (ref "D1")
      (value "SS110B")
      (footprint "eagle-import:SMB")
      (libsource (lib "eagle-import") (part "SCHOTTKYSMB"))
    )
    (comp (ref "D2")
      (value "SS110B")
      (footprint "eagle-import:SMB")
      (libsource (lib "eagle-import") (part "SCHOTTKYSMB"))
    )
    (comp (ref "D3")
      (value "SS110B")
      (footprint "eagle-import:SMB")
      (libsource (lib "eagle-import") (part "SCHOTTKYSMB"))
    )
    (comp (ref "D4")
      (value "US1K-DIO")
      (footprint "eagle-import:DO214AA")
      (libsource (lib "eagle-import") (part "DIODEDO214AA"))
    )
    (comp (ref "D5")
      (value "SS110B")
      (footprint "eagle-import:SMB")
      (libsource (lib "eagle-import") (part "SCHOTTKYSMB"))
    )
    (comp (ref "D6")
      (value "SS110B")
      (footprint "eagle-import:SMB")
      (libsource (lib "eagle-import") (part "SCHOTTKYSMB"))
    )
    (comp (ref "D7")
      (value "SS110B")
      (footprint "eagle-import:SMA")
      (libsource (lib "eagle-import") (part "SCHOTTKYSMA_DO-214AC"))
    )
    (comp (ref "D8")
      (value "BAS316")
      (footprint "eagle-import:SOD323-R")
      (libsource (lib "eagle-import") (part "DIODESOD323R"))
    )
    (comp (ref "D9")
      (value "BAS316")
      (footprint "eagle-import:SOD323-R")
      (libsource (lib "eagle-import") (part "DIODESOD323R"))
    )
    (comp (ref "F1")
      (value "0031.7601")
      (footprint "eagle-import:FUSE_TR5")
      (libsource (lib "eagle-import") (part "FUSE_TR5"))
    )
    (comp (ref "FM1")
      (value "FIDUCIAL_2")
      (footprint "eagle-import:FIDUCIAL_DUAL")
      (libsource (lib "eagle-import") (part "FIDUCIAL_2"))
    )
    (comp (ref "FM2")
      (value "FIDUCIAL_2")
      (footprint "eagle-import:FIDUCIAL_DUAL")
      (libsource (lib "eagle-import") (part "FIDUCIAL_2"))
    )
    (comp (ref "IC1")
      (value "VIPer35L")
      (footprint "eagle-import:SOIC-16")
      (libsource (lib "eagle-import") (part "VIPER35"))
    )
    (comp (ref "JP1")
      (value "JP2-NOCUT")
      (footprint "eagle-import:JP2-NOCUT")
      (libsource (lib "eagle-import") (part "JP2-NOCUT"))
    )
    (comp (ref "JP2")
      (value "JP2-CUT")
      (footprint "eagle-import:JP2-CUT")
      (libsource (lib "eagle-import") (part "JP2-CUT"))
    )
    (comp (ref "JP3")
      (value "JP2-NOCUT")
      (footprint "eagle-import:JP2-NOCUT")
      (libsource (lib "eagle-import") (part "JP2-NOCUT"))
    )
    (comp (ref "JP4")
      (value "0R-JUMPA")
      (footprint "eagle-import:A0R-JMP")
      (libsource (lib "eagle-import") (part "0R-JUMPA"))
    )
    (comp (ref "JP5")
      (value "JP3-CUT")
      (footprint "eagle-import:JP3-CUT")
      (libsource (lib "eagle-import") (part "JP3-CUT"))
    )
    (comp (ref "L1")
      (value "RN214-2.5-02-3M3")
      (footprint "eagle-import:RN214")
      (fields (field (name "FARNELL") "1191518"))
      (libsource (lib "eagle-import") (part "EEZ_inductors_and_transformers_RN214"))
    )
    (comp (ref "L2")
      (value "DLG-0403-180")
      (footprint "eagle-import:DE0403")
      (libsource (lib "eagle-import") (part "EEZ_inductors_and_transformers_DE0403"))
    )
    (comp (ref "L3")
      (value "RLB0812-471KL")
      (footprint "eagle-import:FERSYTER_DSZ6")
      (libsource (lib "eagle-import") (part "FERYSTER_DSZ6"))
    )
    (comp (ref "L4")
      (value "DLG-0403-180")
      (footprint "eagle-import:DE0403")
      (libsource (lib "eagle-import") (part "EEZ_inductors_and_transformers_DE0403"))
    )
    (comp (ref "L5")
      (value "DLG-0403-180")
      (footprint "eagle-import:DE0403")
      (libsource (lib "eagle-import") (part "EEZ_inductors_and_transformers_DE0403"))
    )
    (comp (ref "L6")
      (value "DLG-0403-180")
      (footprint "eagle-import:DE0403")
      (libsource (lib "eagle-import") (part "EEZ_inductors_and_transformers_DE0403"))
    )
    (comp (ref "OK1")
      (value "TLP291-GB.SE-T")
      (footprint "eagle-import:SO4")
      (libsource (lib "eagle-import") (part "TLP291"))
    )
    (comp (ref "Q1")
      (value "MMBT5551")
      (footprint "eagle-import:SOT23-BEC")
      (libsource (lib "eagle-import") (part "-NPN-SOT23-BECMMBT5551LT1"))
    )
    (comp (ref "R1")
      (value "120R")
      (footprint "eagle-import:R0805")
      (libsource (lib "eagle-import") (part "R-EU_R0805"))
    )
    (comp (ref "R2")
      (value "470K")
      (footprint "eagle-import:R1206")
      (libsource (lib "eagle-import") (part "R-EU_R1206"))
    )
    (comp (ref "R3")
      (value "470K")
      (footprint "eagle-import:R1206")
      (libsource (lib "eagle-import") (part "R-EU_R1206"))
    )
    (comp (ref "R4")
      (value "1K8")
      (footprint "eagle-import:R0805")
      (libsource (lib "eagle-import") (part "R-EU_R0805"))
    )
    (comp (ref "R5")
      (value "120R")
      (footprint "eagle-import:R0805")
      (libsource (lib "eagle-import") (part "R-EU_R0805"))
    )
    (comp (ref "R6")
      (value "4K7")
      (footprint "eagle-import:R0805")
      (libsource (lib "eagle-import") (part "R-EU_R0805"))
    )
    (comp (ref "R7")
      (value "4K7")
      (footprint "eagle-import:R0805")
      (libsource (lib "eagle-import") (part "R-EU_R0805"))
    )
    (comp (ref "R8")
      (value "100K")
      (footprint "eagle-import:R1206")
      (libsource (lib "eagle-import") (part "R-EU_R1206"))
    )
    (comp (ref "R9")
      (value "100K")
      (footprint "eagle-import:R1206")
      (libsource (lib "eagle-import") (part "R-EU_R1206"))
    )
    (comp (ref "R10")
      (value "120R")
      (footprint "eagle-import:R0805")
      (libsource (lib "eagle-import") (part "R-EU_R0805"))
    )
    (comp (ref "R11")
      (value "100K")
      (footprint "eagle-import:R1206")
      (libsource (lib "eagle-import") (part "R-EU_R1206"))
    )
    (comp (ref "R12")
      (value "120R")
      (footprint "eagle-import:R0805")
      (libsource (lib "eagle-import") (part "R-EU_R0805"))
    )
    (comp (ref "R13")
      (value "100K")
      (footprint "eagle-import:R1206")
      (libsource (lib "eagle-import") (part "R-EU_R1206"))
    )
    (comp (ref "R14")
      (value "100K")
      (footprint "eagle-import:R1206")
      (libsource (lib "eagle-import") (part "R-EU_R1206"))
    )
    (comp (ref "R15")
      (value "120R")
      (footprint "eagle-import:R0805")
      (libsource (lib "eagle-import") (part "R-EU_R0805"))
    )
    (comp (ref "R16")
      (value "30K")
      (footprint "eagle-import:R0805")
      (libsource (lib "eagle-import") (part "R-EU_R0805"))
    )
    (comp (ref "R17")
      (value "1K")
      (footprint "eagle-import:R0805")
      (libsource (lib "eagle-import") (part "R-EU_R0805"))
    )
    (comp (ref "R18")
      (value "1K8")
      (footprint "eagle-import:R0805")
      (libsource (lib "eagle-import") (part "R-EU_R0805"))
    )
    (comp (ref "R19")
      (value "4K7")
      (footprint "eagle-import:R0805")
      (libsource (lib "eagle-import") (part "R-EU_R0805"))
    )
    (comp (ref "R20")
      (value "47K")
      (footprint "eagle-import:R0805")
      (libsource (lib "eagle-import") (part "R-EU_R0805"))
    )
    (comp (ref "R21")
      (value "1K")
      (footprint "eagle-import:R0805")
      (libsource (lib "eagle-import") (part "R-EU_R0805"))
    )
    (comp (ref "SAR1")
      (value "PCB 2.4mm")
      (footprint "eagle-import:PCB-SAR_2.4MM")
      (libsource (lib "eagle-import") (part "SARPCB-2.4MM"))
    )
    (comp (ref "SAR2")
      (value "PCB 2.4mm")
      (footprint "eagle-import:PCB-SAR_2.4MM")
      (libsource (lib "eagle-import") (part "SARPCB-2.4MM"))
    )
    (comp (ref "TP1")
      (value "PCB_TEST_TABSHIELD")
      (footprint "eagle-import:PCB_SHIELD_TAB")
      (libsource (lib "eagle-import") (part "PCB_TEST_TABSHIELD"))
    )
    (comp (ref "TR1")
      (value "FERYSTER_5851")
      (footprint "eagle-import:FERYSTER_5572")
      (libsource (lib "eagle-import") (part "FERYSTER_5851"))
    )
    (comp (ref "X1")
      (value "39-30-3035")
      (footprint "eagle-import:MINIFIT_6659-3_CRE")
      (libsource (lib "eagle-import") (part "MINIFIT_6659-3-CRE"))
    )
    (comp (ref "ZD1")
      (value "BZT52C13")
      (footprint "eagle-import:SOD123")
      (libsource (lib "eagle-import") (part "ZENER-DIODESOD123"))
    )
    (comp (ref "ZD2")
      (value "BZT52C20-DC")
      (footprint "eagle-import:SOD123")
      (libsource (lib "eagle-import") (part "ZENER-DIODESOD123"))
    )
    (comp (ref "ZD3")
      (value "MMSZ5V1T1G")
      (footprint "eagle-import:SOD123")
      (libsource (lib "eagle-import") (part "ZENER-DIODESOD123"))
    )
  )
  (nets
    (net (code "1") (name "+2.5VREF") (class "Default")
      (node (ref "C81") (pin "1") (pinfunction "1_1") (pintype "passive"))
      (node (ref "IC7") (pin "3") (pinfunction "+IN1_3") (pintype "input"))
      (node (ref "P1") (pin "E") (pinfunction "E_E") (pintype "passive"))
      (node (ref "R81") (pin "2") (pinfunction "2_2") (pintype "passive"))
      (node (ref "R87") (pin "1") (pinfunction "1_1") (pintype "passive"))
    )
    (net (code "2") (name "+5VREF") (class "Default")
      (node (ref "C49") (pin "2") (pinfunction "2_2") (pintype "passive"))
      (node (ref "IC3") (pin "4") (pinfunction "REF_4") (pintype "output"))
      (node (ref "R31") (pin "1") (pinfunction "1_1") (pintype "passive"))
      (node (ref "R58") (pin "2") (pinfunction "2_2") (pintype "passive"))
      (node (ref "R59") (pin "2") (pinfunction "2_2") (pintype "passive"))
      (node (ref "X3") (pin "2") (pinfunction "1_2") (pintype "passive"))
      (node (ref "ZD4") (pin "C") (pinfunction "C_C") (pintype "passive"))
    )
    (net (code "3") (name "+12V") (class "Default")
      (node (ref "C29") (pin "2") (pinfunction "2_2") (pintype "passive"))
      (node (ref "C30") (pin "2") (pinfunction "2_2") (pintype "passive"))
      (node (ref "C53") (pin "1") (pinfunction "1_1") (pintype "passive"))
      (node (ref "C54") (pin "1") (pinfunction "1_1") (pintype "passive"))
      (node (ref "IC4") (pin "8") (pinfunction "V+_8") (pintype "power_in"))
      (node (ref "JP1") (pin "2") (pinfunction "2_2") (pintype "passive"))
      (node (ref "OK2") (pin "1") (pinfunction "A_1") (pintype "passive"))
      (node (ref "R23") (pin "2") (pinfunction "2_2") (pintype "passive"))
      (node (ref "R35") (pin "2") (pinfunction "2_2") (pintype "passive"))
      (node (ref "R43") (pin "2") (pinfunction "2_2") (pintype "passive"))
    )
    (net (code "4") (name "0V") (class "Default")
      (node (ref "C16") (pin "-") (pinfunction "-_-") (pintype "passive"))
      (node (ref "C21") (pin "1") (pinfunction "1_1") (pintype "passive"))
      (node (ref "C24") (pin "2") (pinfunction "-_2") (pintype "passive"))
      (node (ref "C27") (pin "2") (pinfunction "2_2") (pintype "passive"))
      (node (ref "C28") (pin "2") (pinfunction "2_2") (pintype "passive"))
      (node (ref "C29") (pin "1") (pinfunction "1_1") (pintype "passive"))
      (node (ref "C30") (pin "1") (pinfunction "1_1") (pintype "passive"))
      (node (ref "C34") (pin "-") (pinfunction "-_-") (pintype "passive"))
      (node (ref "C35") (pin "-") (pinfunction "-_-") (pintype "passive"))
      (node (ref "C36") (pin "2") (pinfunction "2_2") (pintype "passive"))
      (node (ref "C38") (pin "2") (pinfunction "2_2") (pintype "passive"))
      (node (ref "C39") (pin "2") (pinfunction "2_2") (pintype "passive"))
      (node (ref "C40") (pin "2") (pinfunction "2_2") (pintype "passive"))
      (node (ref "C41") (pin "1") (pinfunction "1_1") (pintype "passive"))
      (node (ref "C43") (pin "2") (pinfunction "2_2") (pintype "passive"))
      (node (ref "C45") (pin "2") (pinfunction "2_2") (pintype "passive"))
      (node (ref "C5") (pin "2") (pinfunction "2_2") (pintype "passive"))
      (node (ref "C6") (pin "2") (pinfunction "-_2") (pintype "passive"))
      (node (ref "C7") (pin "2") (pinfunction "2_2") (pintype "passive"))
      (node (ref "D12") (pin "2") (pinfunction "A_2") (pintype "passive"))
      (node (ref "D9") (pin "A") (pinfunction "A_A") (pintype "passive"))
      (node (ref "IC1") (pin "1") (pinfunction "GND_1") (pintype "passive"))
      (node (ref "IC1") (pin "2") (pinfunction "GND_2") (pintype "passive"))
      (node (ref "IC1") (pin "3") (pinfunction "GND_3") (pintype "passive"))
      (node (ref "IC1") (pin "4") (pinfunction "GND_4") (pintype "passive"))
      (node (ref "IC2") (pin "9") (pinfunction "GNDB_9") (pintype "power_in"))
      (node (ref "JP5") (pin "NC") (pinfunction "NC_NC") (pintype "passive"))
      (node (ref "OK1") (pin "3") (pinfunction "EMIT_3") (pintype "passive"))
      (node (ref "Q3") (pin "S") (pinfunction "S_S") (pintype "passive"))
      (node (ref "Q5") (pin "S") (pinfunction "S_S") (pintype "passive"))
      (node (ref "Q6") (pin "S") (pinfunction "S_S") (pintype "passive"))
      (node (ref "R18") (pin "2") (pinfunction "2_2") (pintype "passive"))
      (node (ref "R19") (pin "1") (pinfunction "1_1") (pintype "passive"))
      (node (ref "R20") (pin "2") (pinfunction "2_2") (pintype "passive"))
      (node (ref "R37") (pin "2") (pinfunction "2_2") (pintype "passive"))
      (node (ref "R38") (pin "1") (pinfunction "1_1") (pintype "passive"))
      (node (ref "R38") (pin "2") (pinfunction "2_2") (pintype "passive"))
      (node (ref "R48") (pin "2") (pinfunction "2_2") (pintype "passive"))
      (node (ref "R54") (pin "2") (pinfunction "2_2") (pintype "passive"))
      (node (ref "SH1") (pin "P$2") (pinfunction "GND_B_P$2") (pintype "bidirectional"))
      (node (ref "SH3") (pin "P$1") (pinfunction "GND_A_P$1") (pintype "bidirectional"))
      (node (ref "TP3") (pin "1") (pinfunction "P$1_1") (pintype "bidirectional"))
      (node (ref "TP4") (pin "1") (pinfunction "P$1_1") (pintype "bidirectional"))
      (node (ref "TR1") (pin "6") (pinfunction "S_AUX_6") (pintype "passive"))
      (node (ref "ZD1") (pin "A") (pinfunction "A_A") (pintype "passive"))
      (node (ref "ZD2") (pin "A") (pinfunction "A_A") (pintype "passive"))
      (node (ref "ZD4") (pin "A") (pinfunction "A_A") (pintype "passive"))
    )
    (net (code "5") (name "12V_COMM") (class "Default")
      (node (ref "C10") (pin "2") (pinfunction "2_2") (pintype "passive"))
      (node (ref "C11") (pin "2") (pinfunction "-_2") (pintype "passive"))
      (node (ref "C12") (pin "1") (pinfunction "+_1") (pintype "passive"))
      (node (ref "C13") (pin "1") (pinfunction "1_1") (pintype "passive"))
      (node (ref "JP4") (pin "2") (pinfunction "2_2") (pintype "passive"))
      (node (ref "R6") (pin "2") (pinfunction "2_2") (pintype "passive"))
      (node (ref "R7") (pin "1") (pinfunction "1_1") (pintype "passive"))
      (node (ref "TR1") (pin "14") (pinfunction "12V_DOT_14") (pintype "passive"))
      (node (ref "X2") (pin "2") (pinfunction "1_2") (pintype "passive"))
    )
    (net (code "6") (name "AC_L_IN") (class "Default")
      (node (ref "C2") (pin "2") (pinfunction "2_2") (pintype "passive"))
      (node (ref "C8") (pin "2") (pinfunction "2_2") (pintype "passive"))
      (node (ref "L1") (pin "2") (pinfunction "2_2") (pintype "passive"))
      (node (ref "R3") (pin "2") (pinfunction "2_2") (pintype "passive"))
      (node (ref "SAR2") (pin "1") (pinfunction "P$1_1") (pintype "bidirectional"))
      (node (ref "X1") (pin "1") (pinfunction "1_1") (pintype "passive"))
    )
    (net (code "7") (name "AC_N_IN") (class "Default")
      (node (ref "C2") (pin "1") (pinfunction "1_1") (pintype "passive"))
      (node (ref "C4") (pin "2") (pinfunction "2_2") (pintype "passive"))
      (node (ref "L1") (pin "4") (pinfunction "2_4") (pintype "passive"))
      (node (ref "R2") (pin "1") (pinfunction "1_1") (pintype "passive"))
      (node (ref "SAR1") (pin "1") (pinfunction "P$1_1") (pintype "bidirectional"))
      (node (ref "X1") (pin "2") (pinfunction "1_2") (pintype "passive"))
    )
    (net (code "8") (name "AGND") (class "Default")
      (node (ref "C37") (pin "1") (pinfunction "1_1") (pintype "passive"))
      (node (ref "C42") (pin "2") (pinfunction "2_2") (pintype "passive"))
      (node (ref "C46") (pin "1") (pinfunction "1_1") (pintype "passive"))
      (node (ref "C47") (pin "2") (pinfunction "2_2") (pintype "passive"))
      (node (ref "C49") (pin "1") (pinfunction "1_1") (pintype "passive"))
      (node (ref "C50") (pin "1") (pinfunction "1_1") (pintype "passive"))
      (node (ref "C51") (pin "1") (pinfunction "1_1") (pintype "passive"))
      (node (ref "C52") (pin "2") (pinfunction "2_2") (pintype "passive"))
      (node (ref "C53") (pin "2") (pinfunction "2_2") (pintype "passive"))
      (node (ref "C55") (pin "2") (pinfunction "2_2") (pintype "passive"))
      (node (ref "C56") (pin "1") (pinfunction "1_1") (pintype "passive"))
      (node (ref "C57") (pin "1") (pinfunction "1_1") (pintype "passive"))
      (node (ref "IC2") (pin "4") (pinfunction "GNDI_4") (pintype "power_in"))
      (node (ref "IC2") (pin "5") (pinfunction "DISABLE_5") (pintype "input"))
      (node (ref "IC3") (pin "10") (pinfunction "PGND_10") (pintype "power_in"))
      (node (ref "IC3") (pin "11") (pinfunction "AGND_11") (pintype "power_in"))
      (node (ref "IC4") (pin "4") (pinfunction "V-_4") (pintype "power_in"))
      (node (ref "OK3") (pin "3") (pinfunction "EMIT_3") (pintype "passive"))
      (node (ref "Q4") (pin "1") (pinfunction "C_1") (pintype "passive"))
      (node (ref "R32") (pin "1") (pinfunction "1_1") (pintype "passive"))
      (node (ref "R33") (pin "1") (pinfunction "1_1") (pintype "passive"))
      (node (ref "R33") (pin "2") (pinfunction "2_2") (pintype "passive"))
      (node (ref "R44") (pin "2") (pinfunction "2_2") (pintype "passive"))
      (node (ref "R49") (pin "2") (pinfunction "2_2") (pintype "passive"))
      (node (ref "R51") (pin "2") (pinfunction "2_2") (pintype "passive"))
      (node (ref "R56") (pin "2") (pinfunction "2_2") (pintype "passive"))
      (node (ref "R57") (pin "2") (pinfunction "2_2") (pintype "passive"))
      (node (ref "R61") (pin "2") (pinfunction "2_2") (pintype "passive"))
      (node (ref "R62") (pin "2") (pinfunction "2_2") (pintype "passive"))
      (node (ref "R63") (pin "2") (pinfunction "2_2") (pintype "passive"))
      (node (ref "R64") (pin "2") (pinfunction "2_2") (pintype "passive"))
      (node (ref "R65") (pin "2") (pinfunction "2_2") (pintype "passive"))
      (node (ref "SH2") (pin "P$2") (pinfunction "GND_B_P$2") (pintype "bidirectional"))
      (node (ref "SH3") (pin "P$2") (pinfunction "GND_B_P$2") (pintype "bidirectional"))
      (node (ref "ZD5") (pin "A") (pinfunction "A_A") (pintype "passive"))
    )
    (net (code "9") (name "AUX_AC") (class "Default")
      (node (ref "C1") (pin "2") (pinfunction "2_2") (pintype "passive"))
      (node (ref "D1") (pin "A") (pinfunction "A_A") (pintype "passive"))
      (node (ref "D7") (pin "A") (pinfunction "A_A") (pintype "passive"))
      (node (ref "D8") (pin "A") (pinfunction "A_A") (pintype "passive"))
      (node (ref "TR1") (pin "7") (pinfunction "S_AUX_DOT_7") (pintype "passive"))
    )
    (net (code "10") (name "BUCK_OUT") (class "Default")
      (node (ref "C31") (pin "2") (pinfunction "2_2") (pintype "passive"))
      (node (ref "C32") (pin "2") (pinfunction "2_2") (pintype "passive"))
      (node (ref "C33") (pin "2") (pinfunction "2_2") (pintype "passive"))
      (node (ref "D12") (pin "1") (pinfunction "C_1") (pintype "passive"))
      (node (ref "IC2") (pin "14") (pinfunction "GNDA_14") (pintype "power_in"))
      (node (ref "L7") (pin "2") (pinfunction "P$2_2") (pintype "bidirectional"))
      (node (ref "L8") (pin "2") (pinfunction "P$2_2") (pintype "bidirectional"))
      (node (ref "Q2") (pin "S") (pinfunction "S_S") (pintype "passive"))
      (node (ref "Q3") (pin "D") (pinfunction "D_D") (pintype "passive"))
    )
    (net (code "11") (name "COMP") (class "Default")
      (node (ref "C50") (pin "2") (pinfunction "2_2") (pintype "passive"))
      (node (ref "IC3") (pin "3") (pinfunction "COMP_3") (pintype "passive"))
      (node (ref "JP10") (pin "1") (pinfunction "1_1") (pintype "passive"))
      (node (ref "R57") (pin "1") (pinfunction "1_1") (pintype "passive"))
    )
    (net (code "12") (name "CT_OUT+") (class "Default")
      (node (ref "D21") (pin "A") (pinfunction "A_A") (pintype "passive"))
      (node (ref "R24") (pin "1") (pinfunction "1_1") (pintype "passive"))
      (node (ref "TR2") (pin "3") (pinfunction "S_3") (pintype "passive"))
    )
    (net (code "13") (name "CT_OUT-") (class "Default")
      (node (ref "R24") (pin "2") (pinfunction "2_2") (pintype "passive"))
      (node (ref "R55") (pin "2") (pinfunction "2_2") (pintype "passive"))
      (node (ref "SH2") (pin "P$1") (pinfunction "GND_A_P$1") (pintype "bidirectional"))
      (node (ref "TR2") (pin "1") (pinfunction "S_DOT_1") (pintype "passive"))
    )
    (net (code "14") (name "DC_BUS") (class "Default")
      (node (ref "B1") (pin "+") (pinfunction "+_+") (pintype "passive"))
      (node (ref "C34") (pin "+") (pinfunction "+_+") (pintype "passive"))
      (node (ref "C35") (pin "+") (pinfunction "+_+") (pintype "passive"))
      (node (ref "C36") (pin "1") (pinfunction "1_1") (pintype "passive"))
      (node (ref "D15") (pin "C") (pinfunction "C_C") (pintype "passive"))
      (node (ref "JP3") (pin "1") (pinfunction "1_1") (pintype "passive"))
      (node (ref "L3") (pin "P$1") (pinfunction "1_P$1") (pintype "passive"))
      (node (ref "R22") (pin "1") (pinfunction "1_1") (pintype "passive"))
      (node (ref "TR2") (pin "7") (pinfunction "P_7") (pintype "passive"))
    )
    (net (code "15") (name "DC_OUT") (class "Default")
      (node (ref "C10") (pin "1") (pinfunction "1_1") (pintype "passive"))
      (node (ref "L2") (pin "2") (pinfunction "2_2") (pintype "passive"))
      (node (ref "R6") (pin "1") (pinfunction "1_1") (pintype "passive"))
      (node (ref "X2") (pin "1") (pinfunction "1_1") (pintype "passive"))
    )
    (net (code "16") (name "ENC_PE") (class "Default")
      (node (ref "JP2") (pin "2") (pinfunction "2_2") (pintype "passive"))
    )
    (net (code "17") (name "FB") (class "Default")
      (node (ref "C52") (pin "1") (pinfunction "1_1") (pintype "passive"))
      (node (ref "IC3") (pin "2") (pinfunction "FB_2") (pintype "input"))
      (node (ref "R45") (pin "1") (pinfunction "1_1") (pintype "passive"))
      (node (ref "R56") (pin "1") (pinfunction "1_1") (pintype "passive"))
      (node (ref "R60") (pin "1") (pinfunction "1_1") (pintype "passive"))
    )
    (net (code "18") (name "GND") (class "Default")
      (node (ref "C18") (pin "1") (pinfunction "+_1") (pintype "passive"))
      (node (ref "C19") (pin "1") (pinfunction "1_1") (pintype "passive"))
      (node (ref "C20") (pin "2") (pinfunction "2_2") (pintype "passive"))
      (node (ref "C23") (pin "-") (pinfunction "-_-") (pintype "passive"))
      (node (ref "C25") (pin "2") (pinfunction "2_2") (pintype "passive"))
      (node (ref "C58") (pin "-") (pinfunction "-_-") (pintype "passive"))
      (node (ref "C59") (pin "2") (pinfunction "2_2") (pintype "passive"))
      (node (ref "C60") (pin "1") (pinfunction "1_1") (pintype "passive"))
      (node (ref "C61") (pin "-") (pinfunction "-_-") (pintype "passive"))
      (node (ref "C62") (pin "2") (pinfunction "2_2") (pintype "passive"))
      (node (ref "C63") (pin "2") (pinfunction "2_2") (pintype "passive"))
      (node (ref "C64") (pin "2") (pinfunction "2_2") (pintype "passive"))
      (node (ref "C65") (pin "1") (pinfunction "1_1") (pintype "passive"))
      (node (ref "C66") (pin "2") (pinfunction "2_2") (pintype "passive"))
      (node (ref "C67") (pin "2") (pinfunction "2_2") (pintype "passive"))
      (node (ref "C70") (pin "1") (pinfunction "1_1") (pintype "passive"))
      (node (ref "C71") (pin "2") (pinfunction "2_2") (pintype "passive"))
      (node (ref "C72") (pin "1") (pinfunction "1_1") (pintype "passive"))
      (node (ref "C73") (pin "2") (pinfunction "2_2") (pintype "passive"))
      (node (ref "C75") (pin "2") (pinfunction "2_2") (pintype "passive"))
      (node (ref "C77") (pin "2") (pinfunction "2_2") (pintype "passive"))
      (node (ref "C80") (pin "-") (pinfunction "-_-") (pintype "passive"))
      (node (ref "C81") (pin "2") (pinfunction "2_2") (pintype "passive"))
      (node (ref "C82") (pin "2") (pinfunction "2_2") (pintype "passive"))
      (node (ref "IC5") (pin "6") (pinfunction "VS_6") (pintype "passive"))
      (node (ref "IC5") (pin "7") (pinfunction "GND_7") (pintype "power_in"))
      (node (ref "IC6") (pin "3") (pinfunction "+IN_3") (pintype "input"))
      (node (ref "IC6") (pin "5") (pinfunction "+IN_5") (pintype "input"))
      (node (ref "IC7") (pin "4") (pinfunction "VCC-_4") (pintype "power_in"))
      (node (ref "JP4") (pin "3") (pinfunction "3_3") (pintype "passive"))
      (node (ref "LED1") (pin "TC") (pinfunction "C_TC") (pintype "passive"))
      (node (ref "OK2") (pin "3") (pinfunction "EMIT_3") (pintype "passive"))
      (node (ref "P1") (pin "A") (pinfunction "A_A") (pintype "passive"))
      (node (ref "Q7") (pin "3") (pinfunction "S_3") (pintype "passive"))
      (node (ref "Q8") (pin "3") (pinfunction "S_3") (pintype "passive"))
      (node (ref "R70") (pin "1") (pinfunction "1_1") (pintype "passive"))
      (node (ref "R73") (pin "2") (pinfunction "2_2") (pintype "passive"))
      (node (ref "TP1") (pin "1") (pinfunction "P$1_1") (pintype "bidirectional"))
      (node (ref "TP5") (pin "GND") (pinfunction "GND_GND") (pintype "bidirectional"))
      (node (ref "TP6") (pin "2") (pinfunction "2_2") (pintype "passive"))
      (node (ref "TR1") (pin "10") (pinfunction "6V_10") (pintype "passive"))
      (node (ref "TR1") (pin "11") (pinfunction "7V_DOT_11") (pintype "passive"))
      (node (ref "X2") (pin "4") (pinfunction "1_4") (pintype "passive"))
      (node (ref "X2") (pin "8") (pinfunction "1_8") (pintype "passive"))
      (node (ref "X4") (pin "2") (pinfunction "1_2") (pintype "passive"))
      (node (ref "ZD3") (pin "A") (pinfunction "A_A") (pintype "passive"))
      (node (ref "ZD6") (pin "A") (pinfunction "A_A") (pintype "passive"))
    )
    (net (code "19") (name "GNDA") (class "Default")
      (node (ref "B1") (pin "-") (pinfunction "-_-") (pintype "passive"))
      (node (ref "SH1") (pin "P$1") (pinfunction "GND_A_P$1") (pintype "bidirectional"))
    )
    (net (code "20") (name "HD") (class "Default")
      (node (ref "IC3") (pin "5") (pinfunction "HD_5") (pintype "output"))
      (node (ref "R28") (pin "2") (pinfunction "2_2") (pintype "passive"))
    )
    (net (code "21") (name "HI_OUT") (class "Default")
      (node (ref "IC2") (pin "15") (pinfunction "VOA_15") (pintype "output"))
      (node (ref "R25") (pin "2") (pinfunction "2_2") (pintype "passive"))
      (node (ref "R26") (pin "2") (pinfunction "2_2") (pintype "passive"))
    )
    (net (code "22") (name "LD") (class "Default")
      (node (ref "IC3") (pin "6") (pinfunction "LD_6") (pintype "output"))
      (node (ref "R29") (pin "2") (pinfunction "2_2") (pintype "passive"))
    )
    (net (code "23") (name "LO_OUT") (class "Default")
      (node (ref "IC2") (pin "10") (pinfunction "VOB_10") (pintype "output"))
      (node (ref "R34") (pin "1") (pinfunction "1_1") (pintype "passive"))
      (node (ref "R36") (pin "1") (pinfunction "1_1") (pintype "passive"))
    )
    (net (code "24") (name "Net-(B1-PadAC2)") (class "Default")
      (node (ref "B1") (pin "AC2") (pinfunction "AC2_AC2") (pintype "passive"))
      (node (ref "F1") (pin "2") (pinfunction "2_2") (pintype "passive"))
    )
    (net (code "25") (name "Net-(C1-Pad1)") (class "Default")
      (node (ref "C1") (pin "1") (pinfunction "1_1") (pintype "passive"))
      (node (ref "R1") (pin "2") (pinfunction "2_2") (pintype "passive"))
    )
    (net (code "26") (name "Net-(C5-Pad1)") (class "Default")
      (node (ref "C5") (pin "1") (pinfunction "1_1") (pintype "passive"))
      (node (ref "JP1") (pin "1") (pinfunction "1_1") (pintype "passive"))
      (node (ref "Q1") (pin "E") (pinfunction "E_E") (pintype "passive"))
    )
    (net (code "27") (name "Net-(C6-+)") (class "Default")
      (node (ref "C6") (pin "1") (pinfunction "+_1") (pintype "passive"))
      (node (ref "D1") (pin "C") (pinfunction "C_C") (pintype "passive"))
      (node (ref "Q1") (pin "C") (pinfunction "C_C") (pintype "passive"))
      (node (ref "R1") (pin "1") (pinfunction "1_1") (pintype "passive"))
      (node (ref "R4") (pin "1") (pinfunction "1_1") (pintype "passive"))
    )
    (net (code "28") (name "Net-(C7-Pad1)") (class "Default")
      (node (ref "C7") (pin "1") (pinfunction "1_1") (pintype "passive"))
      (node (ref "Q1") (pin "B") (pinfunction "B_B") (pintype "passive"))
      (node (ref "R4") (pin "2") (pinfunction "2_2") (pintype "passive"))
      (node (ref "ZD1") (pin "C") (pinfunction "C_C") (pintype "passive"))
    )
    (net (code "29") (name "Net-(C9-Pad1)") (class "Default")
      (node (ref "C9") (pin "1") (pinfunction "1_1") (pintype "passive"))
      (node (ref "R5") (pin "2") (pinfunction "2_2") (pintype "passive"))
    )
    (net (code "30") (name "Net-(C11-+)") (class "Default")
      (node (ref "C11") (pin "1") (pinfunction "+_1") (pintype "passive"))
      (node (ref "D2") (pin "C") (pinfunction "C_C") (pintype "passive"))
      (node (ref "L2") (pin "1") (pinfunction "1_1") (pintype "passive"))
      (node (ref "R5") (pin "1") (pinfunction "1_1") (pintype "passive"))
    )
    (net (code "31") (name "Net-(C12--)") (class "Default")
      (node (ref "C12") (pin "2") (pinfunction "-_2") (pintype "passive"))
      (node (ref "D3") (pin "A") (pinfunction "A_A") (pintype "passive"))
      (node (ref "L4") (pin "1") (pinfunction "1_1") (pintype "passive"))
      (node (ref "R10") (pin "1") (pinfunction "1_1") (pintype "passive"))
    )
    (net (code "32") (name "Net-(C14-Pad2)") (class "Default")
      (node (ref "C14") (pin "2") (pinfunction "2_2") (pintype "passive"))
      (node (ref "D4") (pin "C") (pinfunction "C_C") (pintype "passive"))
      (node (ref "R11") (pin "1") (pinfunction "1_1") (pintype "passive"))
    )
    (net (code "33") (name "Net-(C15-Pad1)") (class "Default")
      (node (ref "C15") (pin "1") (pinfunction "1_1") (pintype "passive"))
      (node (ref "R10") (pin "2") (pinfunction "2_2") (pintype "passive"))
    )
    (net (code "34") (name "Net-(C17-Pad1)") (class "Default")
      (node (ref "C17") (pin "1") (pinfunction "1_1") (pintype "passive"))
      (node (ref "R12") (pin "2") (pinfunction "2_2") (pintype "passive"))
    )
    (net (code "35") (name "Net-(C18--)") (class "Default")
      (node (ref "C18") (pin "2") (pinfunction "-_2") (pintype "passive"))
      (node (ref "D5") (pin "A") (pinfunction "A_A") (pintype "passive"))
      (node (ref "L5") (pin "1") (pinfunction "1_1") (pintype "passive"))
      (node (ref "R12") (pin "1") (pinfunction "1_1") (pintype "passive"))
    )
    (net (code "36") (name "Net-(C20-Pad1)") (class "Default")
      (node (ref "C20") (pin "1") (pinfunction "1_1") (pintype "passive"))
      (node (ref "JP5") (pin "COM") (pinfunction "COM_COM") (pintype "passive"))
    )
    (net (code "37") (name "Net-(C22-Pad1)") (class "Default")
      (node (ref "C22") (pin "1") (pinfunction "1_1") (pintype "passive"))
      (node (ref "R15") (pin "2") (pinfunction "2_2") (pintype "passive"))
    )
    (net (code "38") (name "Net-(C23-Pad+)") (class "Default")
      (node (ref "C23") (pin "+") (pinfunction "+_+") (pintype "passive"))
      (node (ref "D6") (pin "C") (pinfunction "C_C") (pintype "passive"))
      (node (ref "L6") (pin "1") (pinfunction "1_1") (pintype "passive"))
      (node (ref "R15") (pin "1") (pinfunction "1_1") (pintype "passive"))
      (node (ref "R17") (pin "1") (pinfunction "1_1") (pintype "passive"))
    )
    (net (code "39") (name "Net-(C24-+)") (class "Default")
      (node (ref "C21") (pin "2") (pinfunction "2_2") (pintype "passive"))
      (node (ref "C24") (pin "1") (pinfunction "+_1") (pintype "passive"))
      (node (ref "D7") (pin "C") (pinfunction "C_C") (pintype "passive"))
      (node (ref "IC1") (pin "5") (pinfunction "VDD_5") (pintype "power_in"))
      (node (ref "ZD2") (pin "C") (pinfunction "C_C") (pintype "passive"))
    )
    (net (code "40") (name "Net-(C26-Pad1)") (class "Default")
      (node (ref "C26") (pin "1") (pinfunction "1_1") (pintype "passive"))
      (node (ref "R20") (pin "1") (pinfunction "1_1") (pintype "passive"))
    )
    (net (code "41") (name "Net-(C41-Pad2)") (class "Default")
      (node (ref "C41") (pin "2") (pinfunction "2_2") (pintype "passive"))
      (node (ref "D16") (pin "1") (pinfunction "C_1") (pintype "passive"))
      (node (ref "D16") (pin "3") (pinfunction "C_3") (pintype "passive"))
      (node (ref "D19") (pin "1") (pinfunction "C_1") (pintype "passive"))
      (node (ref "D19") (pin "3") (pinfunction "C_3") (pintype "passive"))
      (node (ref "R39") (pin "1") (pinfunction "1_1") (pintype "passive"))
      (node (ref "R41") (pin "1") (pinfunction "1_1") (pintype "passive"))
      (node (ref "R46") (pin "2") (pinfunction "2_2") (pintype "passive"))
    )
    (net (code "42") (name "Net-(C42-Pad1)") (class "Default")
      (node (ref "C42") (pin "1") (pinfunction "1_1") (pintype "passive"))
      (node (ref "D18") (pin "A") (pinfunction "A_A") (pintype "passive"))
      (node (ref "R30") (pin "2") (pinfunction "2_2") (pintype "passive"))
      (node (ref "R42") (pin "2") (pinfunction "2_2") (pintype "passive"))
      (node (ref "R44") (pin "1") (pinfunction "1_1") (pintype "passive"))
      (node (ref "TP2") (pin "2") (pinfunction "2_2") (pintype "passive"))
    )
    (net (code "43") (name "Net-(C44-Pad1)") (class "Default")
      (node (ref "C44") (pin "1") (pinfunction "1_1") (pintype "passive"))
      (node (ref "R48") (pin "1") (pinfunction "1_1") (pintype "passive"))
    )
    (net (code "44") (name "Net-(C48-Pad1)") (class "Default")
      (node (ref "C48") (pin "1") (pinfunction "1_1") (pintype "passive"))
      (node (ref "R54") (pin "1") (pinfunction "1_1") (pintype "passive"))
    )
    (net (code "45") (name "Net-(C54-Pad2)") (class "Default")
      (node (ref "C54") (pin "2") (pinfunction "2_2") (pintype "passive"))
      (node (ref "D24") (pin "A") (pinfunction "A_A") (pintype "passive"))
      (node (ref "R65") (pin "1") (pinfunction "1_1") (pintype "passive"))
    )
    (net (code "46") (name "Net-(C64-Pad1)") (class "Default")
      (node (ref "C64") (pin "1") (pinfunction "1_1") (pintype "passive"))
      (node (ref "R67") (pin "2") (pinfunction "2_2") (pintype "passive"))
    )
    (net (code "47") (name "Net-(C65-Pad2)") (class "Default")
      (node (ref "C65") (pin "2") (pinfunction "2_2") (pintype "passive"))
      (node (ref "R68") (pin "1") (pinfunction "1_1") (pintype "passive"))
    )
    (net (code "48") (name "Net-(C71-Pad1)") (class "Default")
      (node (ref "C71") (pin "1") (pinfunction "1_1") (pintype "passive"))
      (node (ref "R76") (pin "2") (pinfunction "2_2") (pintype "passive"))
    )
    (net (code "49") (name "Net-(C74-Pad1)") (class "Default")
      (node (ref "C74") (pin "1") (pinfunction "1_1") (pintype "passive"))
      (node (ref "JP6") (pin "COM") (pinfunction "COM_COM") (pintype "passive"))
    )
    (net (code "50") (name "Net-(C74-Pad2)") (class "Default")
      (node (ref "C74") (pin "2") (pinfunction "2_2") (pintype "passive"))
      (node (ref "R83") (pin "2") (pinfunction "2_2") (pintype "passive"))
    )
    (net (code "51") (name "Net-(C79-Pad2)") (class "Default")
      (node (ref "C79") (pin "2") (pinfunction "2_2") (pintype "passive"))
      (node (ref "R86") (pin "2") (pinfunction "2_2") (pintype "passive"))
    )
    (net (code "52") (name "Net-(C80-Pad+)") (class "Default")
      (node (ref "C80") (pin "+") (pinfunction "+_+") (pintype "passive"))
      (node (ref "R85") (pin "1") (pinfunction "1_1") (pintype "passive"))
      (node (ref "R91") (pin "1") (pinfunction "1_1") (pintype "passive"))
      (node (ref "R92") (pin "1") (pinfunction "1_1") (pintype "passive"))
    )
    (net (code "53") (name "Net-(D8-PadC)") (class "Default")
      (node (ref "D8") (pin "C") (pinfunction "C_C") (pintype "passive"))
      (node (ref "D9") (pin "C") (pinfunction "C_C") (pintype "passive"))
      (node (ref "R16") (pin "2") (pinfunction "2_2") (pintype "passive"))
    )
    (net (code "54") (name "Net-(D10-A)") (class "Default")
      (node (ref "D10") (pin "2") (pinfunction "A_2") (pintype "passive"))
      (node (ref "R23") (pin "1") (pinfunction "1_1") (pintype "passive"))
    )
    (net (code "55") (name "Net-(D11-PadA)") (class "Default")
      (node (ref "D11") (pin "A") (pinfunction "A_A") (pintype "passive"))
      (node (ref "Q2") (pin "G") (pinfunction "G_G") (pintype "passive"))
      (node (ref "R25") (pin "1") (pinfunction "1_1") (pintype "passive"))
    )
    (net (code "56") (name "Net-(D11-PadC)") (class "Default")
      (node (ref "D11") (pin "C") (pinfunction "C_C") (pintype "passive"))
      (node (ref "R26") (pin "1") (pinfunction "1_1") (pintype "passive"))
    )
    (net (code "57") (name "Net-(D13-PadA)") (class "Default")
      (node (ref "D13") (pin "A") (pinfunction "A_A") (pintype "passive"))
      (node (ref "R35") (pin "1") (pinfunction "1_1") (pintype "passive"))
    )
    (net (code "58") (name "Net-(D14-PadA)") (class "Default")
      (node (ref "D14") (pin "A") (pinfunction "A_A") (pintype "passive"))
      (node (ref "Q3") (pin "G") (pinfunction "G_G") (pintype "passive"))
      (node (ref "R34") (pin "2") (pinfunction "2_2") (pintype "passive"))
      (node (ref "R37") (pin "1") (pinfunction "1_1") (pintype "passive"))
    )
    (net (code "59") (name "Net-(D14-PadC)") (class "Default")
      (node (ref "D14") (pin "C") (pinfunction "C_C") (pintype "passive"))
      (node (ref "R36") (pin "2") (pinfunction "2_2") (pintype "passive"))
    )
    (net (code "60") (name "Net-(D15-PadA)") (class "Default")
      (node (ref "D15") (pin "A") (pinfunction "A_A") (pintype "passive"))
      (node (ref "R39") (pin "2") (pinfunction "2_2") (pintype "passive"))
      (node (ref "R41") (pin "2") (pinfunction "2_2") (pintype "passive"))
    )
    (net (code "61") (name "Net-(D16-A)") (class "Default")
      (node (ref "C44") (pin "2") (pinfunction "2_2") (pintype "passive"))
      (node (ref "D16") (pin "2") (pinfunction "A_2") (pintype "passive"))
      (node (ref "L7") (pin "1") (pinfunction "P$1_1") (pintype "bidirectional"))
      (node (ref "Q5") (pin "D") (pinfunction "D_D") (pintype "passive"))
      (node (ref "TR3") (pin "P1") (pinfunction "P_P1") (pintype "passive"))
    )
    (net (code "62") (name "Net-(D17-PadA)") (class "Default")
      (node (ref "D17") (pin "A") (pinfunction "A_A") (pintype "passive"))
      (node (ref "R40") (pin "2") (pinfunction "2_2") (pintype "passive"))
    )
    (net (code "63") (name "Net-(D19-A)") (class "Default")
      (node (ref "C48") (pin "2") (pinfunction "2_2") (pintype "passive"))
      (node (ref "D19") (pin "2") (pinfunction "A_2") (pintype "passive"))
      (node (ref "L8") (pin "1") (pinfunction "P$1_1") (pintype "bidirectional"))
      (node (ref "Q6") (pin "D") (pinfunction "D_D") (pintype "passive"))
      (node (ref "TR3") (pin "P1_DOT") (pinfunction "P_DOT_P1_DOT") (pintype "passive"))
    )
    (net (code "64") (name "Net-(D20-PadC)") (class "Default")
      (node (ref "D20") (pin "C") (pinfunction "C_C") (pintype "passive"))
      (node (ref "Q5") (pin "G") (pinfunction "G_G") (pintype "passive"))
      (node (ref "R47") (pin "1") (pinfunction "1_1") (pintype "passive"))
    )
    (net (code "65") (name "Net-(D21-PadC)") (class "Default")
      (node (ref "D21") (pin "C") (pinfunction "C_C") (pintype "passive"))
      (node (ref "R52") (pin "1") (pinfunction "1_1") (pintype "passive"))
      (node (ref "R55") (pin "1") (pinfunction "1_1") (pintype "passive"))
    )
    (net (code "66") (name "Net-(D22-PadC)") (class "Default")
      (node (ref "D22") (pin "C") (pinfunction "C_C") (pintype "passive"))
      (node (ref "Q6") (pin "G") (pinfunction "G_G") (pintype "passive"))
      (node (ref "R53") (pin "1") (pinfunction "1_1") (pintype "passive"))
    )
    (net (code "67") (name "Net-(D23-PadC)") (class "Default")
      (node (ref "D23") (pin "C") (pinfunction "C_C") (pintype "passive"))
      (node (ref "D25") (pin "C") (pinfunction "C_C") (pintype "passive"))
      (node (ref "R50") (pin "2") (pinfunction "2_2") (pintype "passive"))
      (node (ref "R61") (pin "1") (pinfunction "1_1") (pintype "passive"))
    )
    (net (code "68") (name "Net-(IC1-BR)") (class "Default")
      (node (ref "IC1") (pin "8") (pinfunction "BR_8") (pintype "input"))
      (node (ref "R14") (pin "2") (pinfunction "2_2") (pintype "passive"))
      (node (ref "R18") (pin "1") (pinfunction "1_1") (pintype "passive"))
    )
    (net (code "69") (name "Net-(IC1-FB)") (class "Default")
      (node (ref "C26") (pin "2") (pinfunction "2_2") (pintype "passive"))
      (node (ref "C28") (pin "1") (pinfunction "1_1") (pintype "passive"))
      (node (ref "IC1") (pin "7") (pinfunction "FB_7") (pintype "input"))
      (node (ref "OK1") (pin "4") (pinfunction "COL_4") (pintype "passive"))
    )
    (net (code "70") (name "Net-(IC1-ZCD)") (class "Default")
      (node (ref "C27") (pin "1") (pinfunction "1_1") (pintype "passive"))
      (node (ref "IC1") (pin "6") (pinfunction "ZCD_6") (pintype "input"))
      (node (ref "R16") (pin "1") (pinfunction "1_1") (pintype "passive"))
      (node (ref "R19") (pin "2") (pinfunction "2_2") (pintype "passive"))
    )
    (net (code "71") (name "Net-(IC2-DT)") (class "Default")
      (node (ref "IC2") (pin "6") (pinfunction "DT_6") (pintype "input"))
      (node (ref "R32") (pin "2") (pinfunction "2_2") (pintype "passive"))
    )
    (net (code "72") (name "Net-(IC2-VDDA)") (class "Default")
      (node (ref "C31") (pin "1") (pinfunction "1_1") (pintype "passive"))
      (node (ref "C32") (pin "1") (pinfunction "1_1") (pintype "passive"))
      (node (ref "C33") (pin "1") (pinfunction "1_1") (pintype "passive"))
      (node (ref "D10") (pin "1") (pinfunction "C_1") (pintype "passive"))
      (node (ref "D10") (pin "3") (pinfunction "C_3") (pintype "passive"))
      (node (ref "IC2") (pin "16") (pinfunction "VDDA_16") (pintype "power_in"))
    )
    (net (code "73") (name "Net-(IC2-VDDB)") (class "Default")
      (node (ref "C38") (pin "1") (pinfunction "1_1") (pintype "passive"))
      (node (ref "C39") (pin "1") (pinfunction "1_1") (pintype "passive"))
      (node (ref "C40") (pin "1") (pinfunction "1_1") (pintype "passive"))
      (node (ref "D13") (pin "C") (pinfunction "C_C") (pintype "passive"))
      (node (ref "IC2") (pin "11") (pinfunction "VDDB_11") (pintype "power_in"))
    )
    (net (code "74") (name "Net-(IC2-VIA)") (class "Default")
      (node (ref "IC2") (pin "1") (pinfunction "VIA_1") (pintype "input"))
      (node (ref "R28") (pin "1") (pinfunction "1_1") (pintype "passive"))
    )
    (net (code "75") (name "Net-(IC2-VIB)") (class "Default")
      (node (ref "IC2") (pin "2") (pinfunction "VIB_2") (pintype "input"))
      (node (ref "R29") (pin "1") (pinfunction "1_1") (pintype "passive"))
    )
    (net (code "76") (name "Net-(IC3-CS)") (class "Default")
      (node (ref "C51") (pin "2") (pinfunction "2_2") (pintype "passive"))
      (node (ref "IC3") (pin "12") (pinfunction "CS_12") (pintype "input"))
      (node (ref "R52") (pin "2") (pinfunction "2_2") (pintype "passive"))
    )
    (net (code "77") (name "Net-(IC3-RT{slash}SYNC)") (class "Default")
      (node (ref "IC3") (pin "15") (pinfunction "RT/SYNC_15") (pintype "input"))
      (node (ref "R51") (pin "1") (pinfunction "1_1") (pintype "passive"))
    )
    (net (code "78") (name "Net-(IC3-SS)") (class "Default")
      (node (ref "C46") (pin "2") (pinfunction "2_2") (pintype "passive"))
      (node (ref "IC3") (pin "13") (pinfunction "SS_13") (pintype "passive"))
    )
    (net (code "79") (name "Net-(IC3-TIME)") (class "Default")
      (node (ref "IC3") (pin "14") (pinfunction "TIME_14") (pintype "input"))
      (node (ref "R49") (pin "1") (pinfunction "1_1") (pintype "passive"))
    )
    (net (code "80") (name "Net-(IC3-UVLO)") (class "Default")
      (node (ref "IC3") (pin "16") (pinfunction "UVLO_16") (pintype "input"))
      (node (ref "R42") (pin "1") (pinfunction "1_1") (pintype "passive"))
      (node (ref "ZD5") (pin "C") (pinfunction "C_C") (pintype "passive"))
    )
    (net (code "81") (name "Net-(IC3-VCC)") (class "Default")
      (node (ref "C43") (pin "1") (pinfunction "1_1") (pintype "passive"))
      (node (ref "C45") (pin "1") (pinfunction "1_1") (pintype "passive"))
      (node (ref "IC3") (pin "1") (pinfunction "VIN_1") (pintype "input"))
      (node (ref "IC3") (pin "7") (pinfunction "VCC_7") (pintype "power_in"))
      (node (ref "R43") (pin "1") (pinfunction "1_1") (pintype "passive"))
    )
    (net (code "82") (name "Net-(IC4A-+IN)") (class "Default")
      (node (ref "C57") (pin "2") (pinfunction "2_2") (pintype "passive"))
      (node (ref "IC4") (pin "3") (pinfunction "+IN_3") (pintype "input"))
      (node (ref "R60") (pin "2") (pinfunction "2_2") (pintype "passive"))
    )
    (net (code "83") (name "Net-(IC4A--IN)") (class "Default")
      (node (ref "C55") (pin "1") (pinfunction "1_1") (pintype "passive"))
      (node (ref "D24") (pin "C") (pinfunction "C_C") (pintype "passive"))
      (node (ref "IC4") (pin "2") (pinfunction "-IN_2") (pintype "input"))
      (node (ref "R59") (pin "1") (pinfunction "1_1") (pintype "passive"))
      (node (ref "R64") (pin "1") (pinfunction "1_1") (pintype "passive"))
    )
    (net (code "84") (name "Net-(IC4A-OUT)") (class "Default")
      (node (ref "D23") (pin "A") (pinfunction "A_A") (pintype "passive"))
      (node (ref "IC4") (pin "1") (pinfunction "OUT_1") (pintype "output"))
    )
    (net (code "85") (name "Net-(IC4B-+IN)") (class "Default")
      (node (ref "C56") (pin "2") (pinfunction "2_2") (pintype "passive"))
      (node (ref "IC4") (pin "5") (pinfunction "+IN_5") (pintype "input"))
      (node (ref "R63") (pin "1") (pinfunction "1_1") (pintype "passive"))
      (node (ref "X3") (pin "1") (pinfunction "1_1") (pintype "passive"))
    )
    (net (code "86") (name "Net-(IC4B--IN)") (class "Default")
      (node (ref "IC4") (pin "6") (pinfunction "-IN_6") (pintype "input"))
      (node (ref "R58") (pin "1") (pinfunction "1_1") (pintype "passive"))
      (node (ref "R62") (pin "1") (pinfunction "1_1") (pintype "passive"))
    )
    (net (code "87") (name "Net-(IC4B-OUT)") (class "Default")
      (node (ref "D25") (pin "A") (pinfunction "A_A") (pintype "passive"))
      (node (ref "IC4") (pin "7") (pinfunction "OUT_7") (pintype "output"))
    )
    (net (code "88") (name "Net-(IC5-GATE1)") (class "Default")
      (node (ref "IC5") (pin "1") (pinfunction "GATE1_1") (pintype "output"))
      (node (ref "R71") (pin "2") (pinfunction "2_2") (pintype "passive"))
    )
    (net (code "89") (name "Net-(IC5-GATE2)") (class "Default")
      (node (ref "IC5") (pin "8") (pinfunction "GATE2_8") (pintype "output"))
      (node (ref "R74") (pin "2") (pinfunction "2_2") (pintype "passive"))
    )
    (net (code "90") (name "Net-(IC5-MOT)") (class "Default")
      (node (ref "IC5") (pin "3") (pinfunction "MOT_3") (pintype "passive"))
      (node (ref "R73") (pin "1") (pinfunction "1_1") (pintype "passive"))
    )
    (net (code "91") (name "Net-(IC5-VCC)") (class "Default")
      (node (ref "C66") (pin "1") (pinfunction "1_1") (pintype "passive"))
      (node (ref "C67") (pin "1") (pinfunction "1_1") (pintype "passive"))
      (node (ref "IC5") (pin "2") (pinfunction "VCC_2") (pintype "power_in"))
      (node (ref "R72") (pin "2") (pinfunction "2_2") (pintype "passive"))
    )
    (net (code "92") (name "Net-(IC5-VD1)") (class "Default")
      (node (ref "C60") (pin "2") (pinfunction "2_2") (pintype "passive"))
      (node (ref "IC5") (pin "4") (pinfunction "VD1_4") (pintype "passive"))
      (node (ref "R69") (pin "1") (pinfunction "1_1") (pintype "passive"))
    )
    (net (code "93") (name "Net-(IC5-VD2)") (class "Default")
      (node (ref "C72") (pin "2") (pinfunction "2_2") (pintype "passive"))
      (node (ref "IC5") (pin "5") (pinfunction "VD2_5") (pintype "passive"))
      (node (ref "R75") (pin "2") (pinfunction "2_2") (pintype "passive"))
    )
    (net (code "94") (name "Net-(IC6A--IN)") (class "Default")
      (node (ref "C78") (pin "2") (pinfunction "2_2") (pintype "passive"))
      (node (ref "IC6") (pin "2") (pinfunction "-IN_2") (pintype "input"))
      (node (ref "R82") (pin "1") (pinfunction "1_1") (pintype "passive"))
      (node (ref "R85") (pin "2") (pinfunction "2_2") (pintype "passive"))
      (node (ref "R89") (pin "1") (pinfunction "1_1") (pintype "passive"))
    )
    (net (code "95") (name "Net-(IC6A-OUT)") (class "Default")
      (node (ref "C78") (pin "1") (pinfunction "1_1") (pintype "passive"))
      (node (ref "IC6") (pin "1") (pinfunction "OUT_1") (pintype "output"))
      (node (ref "R92") (pin "2") (pinfunction "2_2") (pintype "passive"))
    )
    (net (code "96") (name "Net-(IC6B--IN)") (class "Default")
      (node (ref "IC6") (pin "6") (pinfunction "-IN_6") (pintype "input"))
      (node (ref "R77") (pin "2") (pinfunction "2_2") (pintype "passive"))
      (node (ref "R81") (pin "1") (pinfunction "1_1") (pintype "passive"))
    )
    (net (code "97") (name "Net-(IC6B-OUT)") (class "Default")
      (node (ref "IC6") (pin "7") (pinfunction "OUT_7") (pintype "output"))
      (node (ref "R77") (pin "1") (pinfunction "1_1") (pintype "passive"))
      (node (ref "R82") (pin "2") (pinfunction "2_2") (pintype "passive"))
    )
    (net (code "98") (name "Net-(IC6C-V+)") (class "Default")
      (node (ref "C73") (pin "1") (pinfunction "1_1") (pintype "passive"))
      (node (ref "C75") (pin "1") (pinfunction "1_1") (pintype "passive"))
      (node (ref "IC6") (pin "8") (pinfunction "V+_8") (pintype "power_in"))
      (node (ref "IC7") (pin "8") (pinfunction "VCC+_8") (pintype "power_in"))
      (node (ref "JP7") (pin "2") (pinfunction "2_2") (pintype "passive"))
      (node (ref "R72") (pin "1") (pinfunction "1_1") (pintype "passive"))
      (node (ref "R87") (pin "2") (pinfunction "2_2") (pintype "passive"))
      (node (ref "R88") (pin "2") (pinfunction "2_2") (pintype "passive"))
    )
    (net (code "99") (name "Net-(IC6C-V-)") (class "Default")
      (node (ref "C77") (pin "1") (pinfunction "1_1") (pintype "passive"))
      (node (ref "IC6") (pin "4") (pinfunction "V-_4") (pintype "power_in"))
      (node (ref "JP8") (pin "1") (pinfunction "1_1") (pintype "passive"))
    )
    (net (code "100") (name "Net-(IC7A--IN1)") (class "Default")
      (node (ref "C76") (pin "2") (pinfunction "2_2") (pintype "passive"))
      (node (ref "IC7") (pin "2") (pinfunction "-IN1_2") (pintype "input"))
      (node (ref "R86") (pin "1") (pinfunction "1_1") (pintype "passive"))
      (node (ref "R90") (pin "1") (pinfunction "1_1") (pintype "passive"))
    )
    (net (code "101") (name "Net-(IC7A-OUT1)") (class "Default")
      (node (ref "C76") (pin "1") (pinfunction "1_1") (pintype "passive"))
      (node (ref "C79") (pin "1") (pinfunction "1_1") (pintype "passive"))
      (node (ref "IC7") (pin "1") (pinfunction "OUT1_1") (pintype "output"))
      (node (ref "OK3") (pin "2") (pinfunction "C_2") (pintype "passive"))
    )
    (net (code "102") (name "Net-(IC7B-+IN)") (class "Default")
      (node (ref "C82") (pin "1") (pinfunction "1_1") (pintype "passive"))
      (node (ref "IC7") (pin "5") (pinfunction "+IN_5") (pintype "input"))
      (node (ref "JP9") (pin "COM") (pinfunction "COM_COM") (pintype "passive"))
    )
    (net (code "103") (name "Net-(IC7B--IN)") (class "Default")
      (node (ref "IC7") (pin "6") (pinfunction "-IN_6") (pintype "input"))
      (node (ref "IC7") (pin "7") (pinfunction "OUT_7") (pintype "output"))
      (node (ref "R89") (pin "2") (pinfunction "2_2") (pintype "passive"))
    )
    (net (code "104") (name "Net-(JP9-PadNO)") (class "Default")
      (node (ref "JP9") (pin "NO") (pinfunction "NO_NO") (pintype "passive"))
      (node (ref "P1") (pin "S") (pinfunction "S_S") (pintype "passive"))
    )
    (net (code "105") (name "Net-(L1B-1)") (class "Default")
      (node (ref "B1") (pin "AC1") (pinfunction "AC1_AC1") (pintype "passive"))
      (node (ref "C3") (pin "1") (pinfunction "1_1") (pintype "passive"))
      (node (ref "L1") (pin "3") (pinfunction "1_3") (pintype "passive"))
      (node (ref "SAR1") (pin "2") (pinfunction "P$2_2") (pintype "bidirectional"))
    )
    (net (code "106") (name "Net-(L3-2)") (class "Default")
      (node (ref "C14") (pin "1") (pinfunction "1_1") (pintype "passive"))
      (node (ref "C16") (pin "+") (pinfunction "+_+") (pintype "passive"))
      (node (ref "JP3") (pin "2") (pinfunction "2_2") (pintype "passive"))
      (node (ref "L3") (pin "P$2") (pinfunction "2_P$2") (pintype "passive"))
      (node (ref "R8") (pin "1") (pinfunction "1_1") (pintype "passive"))
      (node (ref "R9") (pin "1") (pinfunction "1_1") (pintype "passive"))
      (node (ref "TR1") (pin "1") (pinfunction "SHIELD_1") (pintype "passive"))
      (node (ref "TR1") (pin "2") (pinfunction "P_2") (pintype "passive"))
    )
    (net (code "107") (name "Net-(LED1A-A)") (class "Default")
      (node (ref "LED1") (pin "BA") (pinfunction "A_BA") (pintype "passive"))
      (node (ref "R78") (pin "2") (pinfunction "2_2") (pintype "passive"))
    )
    (net (code "108") (name "Net-(LED1B-A)") (class "Default")
      (node (ref "LED1") (pin "TA") (pinfunction "A_TA") (pintype "passive"))
      (node (ref "R79") (pin "2") (pinfunction "2_2") (pintype "passive"))
    )
    (net (code "109") (name "Net-(OK1-A)") (class "Default")
      (node (ref "OK1") (pin "1") (pinfunction "A_1") (pintype "passive"))
      (node (ref "R17") (pin "2") (pinfunction "2_2") (pintype "passive"))
    )
    (net (code "110") (name "Net-(OK1-C)") (class "Default")
      (node (ref "OK1") (pin "2") (pinfunction "C_2") (pintype "passive"))
      (node (ref "R21") (pin "1") (pinfunction "1_1") (pintype "passive"))
      (node (ref "ZD3") (pin "C") (pinfunction "C_C") (pintype "passive"))
    )
    (net (code "111") (name "Net-(OK2-C)") (class "Default")
      (node (ref "OK2") (pin "2") (pinfunction "C_2") (pintype "passive"))
      (node (ref "R40") (pin "1") (pinfunction "1_1") (pintype "passive"))
    )
    (net (code "112") (name "Net-(OK3-A)") (class "Default")
      (node (ref "OK3") (pin "1") (pinfunction "A_1") (pintype "passive"))
      (node (ref "R88") (pin "1") (pinfunction "1_1") (pintype "passive"))
    )
    (net (code "113") (name "Net-(OK3-COL)") (class "Default")
      (node (ref "JP10") (pin "2") (pinfunction "2_2") (pintype "passive"))
      (node (ref "OK3") (pin "4") (pinfunction "COL_4") (pintype "passive"))
    )
    (net (code "114") (name "Net-(Q4-A)") (class "Default")
      (node (ref "D17") (pin "C") (pinfunction "C_C") (pintype "passive"))
      (node (ref "D18") (pin "C") (pinfunction "C_C") (pintype "passive"))
      (node (ref "Q4") (pin "3") (pinfunction "A_3") (pintype "passive"))
    )
    (net (code "115") (name "Net-(Q4-G)") (class "Default")
      (node (ref "C47") (pin "1") (pinfunction "1_1") (pintype "passive"))
      (node (ref "Q4") (pin "2") (pinfunction "G_2") (pintype "passive"))
      (node (ref "R50") (pin "1") (pinfunction "1_1") (pintype "passive"))
    )
    (net (code "116") (name "Net-(Q7-G)") (class "Default")
      (node (ref "Q7") (pin "1") (pinfunction "G_1") (pintype "passive"))
      (node (ref "R71") (pin "1") (pinfunction "1_1") (pintype "passive"))
    )
    (net (code "117") (name "Net-(Q8-G)") (class "Default")
      (node (ref "Q8") (pin "1") (pinfunction "G_1") (pintype "passive"))
      (node (ref "R74") (pin "1") (pinfunction "1_1") (pintype "passive"))
    )
    (net (code "118") (name "Net-(R2-Pad2)") (class "Default")
      (node (ref "R2") (pin "2") (pinfunction "2_2") (pintype "passive"))
      (node (ref "R3") (pin "1") (pinfunction "1_1") (pintype "passive"))
    )
    (net (code "119") (name "Net-(R11-Pad2)") (class "Default")
      (node (ref "R11") (pin "2") (pinfunction "2_2") (pintype "passive"))
      (node (ref "R8") (pin "2") (pinfunction "2_2") (pintype "passive"))
    )
    (net (code "120") (name "Net-(R13-Pad1)") (class "Default")
      (node (ref "R13") (pin "1") (pinfunction "1_1") (pintype "passive"))
      (node (ref "R9") (pin "2") (pinfunction "2_2") (pintype "passive"))
    )
    (net (code "121") (name "Net-(R13-Pad2)") (class "Default")
      (node (ref "R13") (pin "2") (pinfunction "2_2") (pintype "passive"))
      (node (ref "R14") (pin "1") (pinfunction "1_1") (pintype "passive"))
    )
    (net (code "122") (name "Net-(R22-Pad2)") (class "Default")
      (node (ref "R22") (pin "2") (pinfunction "2_2") (pintype "passive"))
      (node (ref "R27") (pin "1") (pinfunction "1_1") (pintype "passive"))
    )
    (net (code "123") (name "Net-(R27-Pad2)") (class "Default")
      (node (ref "R27") (pin "2") (pinfunction "2_2") (pintype "passive"))
      (node (ref "R30") (pin "1") (pinfunction "1_1") (pintype "passive"))
      (node (ref "TP2") (pin "1") (pinfunction "1_1") (pintype "passive"))
    )
    (net (code "124") (name "Net-(R45-Pad2)") (class "Default")
      (node (ref "R45") (pin "2") (pinfunction "2_2") (pintype "passive"))
      (node (ref "R46") (pin "1") (pinfunction "1_1") (pintype "passive"))
    )
    (net (code "125") (name "Net-(R80-Pad1)") (class "Default")
      (node (ref "R80") (pin "1") (pinfunction "1_1") (pintype "passive"))
      (node (ref "R84") (pin "2") (pinfunction "2_2") (pintype "passive"))
    )
    (net (code "126") (name "Net-(R83-Pad1)") (class "Default")
      (node (ref "R83") (pin "1") (pinfunction "1_1") (pintype "passive"))
      (node (ref "R84") (pin "1") (pinfunction "1_1") (pintype "passive"))
      (node (ref "R90") (pin "2") (pinfunction "2_2") (pintype "passive"))
      (node (ref "R91") (pin "2") (pinfunction "2_2") (pintype "passive"))
      (node (ref "R93") (pin "2") (pinfunction "2_2") (pintype "passive"))
    )
    (net (code "127") (name "Net-(R93-Pad1)") (class "Default")
      (node (ref "R93") (pin "1") (pinfunction "1_1") (pintype "passive"))
      (node (ref "R94") (pin "2") (pinfunction "2_2") (pintype "passive"))
    )
    (net (code "128") (name "Net-(R94-Pad1)") (class "Default")
      (node (ref "R94") (pin "1") (pinfunction "1_1") (pintype "passive"))
      (node (ref "TP6") (pin "1") (pinfunction "1_1") (pintype "passive"))
    )
    (net (code "129") (name "Net-(SAR2-P$2)") (class "Default")
      (node (ref "C3") (pin "2") (pinfunction "2_2") (pintype "passive"))
      (node (ref "F1") (pin "1") (pinfunction "1_1") (pintype "passive"))
      (node (ref "L1") (pin "1") (pinfunction "1_1") (pintype "passive"))
      (node (ref "SAR2") (pin "2") (pinfunction "P$2_2") (pintype "bidirectional"))
    )
    (net (code "130") (name "Net-(TR1-6V_DOT)") (class "Default")
      (node (ref "C22") (pin "2") (pinfunction "2_2") (pintype "passive"))
      (node (ref "D6") (pin "A") (pinfunction "A_A") (pintype "passive"))
      (node (ref "TR1") (pin "12") (pinfunction "6V_DOT_12") (pintype "passive"))
    )
    (net (code "131") (name "Net-(TR1-7V)") (class "Default")
      (node (ref "C17") (pin "2") (pinfunction "2_2") (pintype "passive"))
      (node (ref "D5") (pin "C") (pinfunction "C_C") (pintype "passive"))
      (node (ref "TR1") (pin "9") (pinfunction "7V_9") (pintype "passive"))
    )
    (net (code "132") (name "Net-(TR1-12V)") (class "Default")
      (node (ref "C15") (pin "2") (pinfunction "2_2") (pintype "passive"))
      (node (ref "D3") (pin "C") (pinfunction "C_C") (pintype "passive"))
      (node (ref "TR1") (pin "13") (pinfunction "12V_13") (pintype "passive"))
    )
    (net (code "133") (name "Net-(TR1-12V_DOT2)") (class "Default")
      (node (ref "C9") (pin "2") (pinfunction "2_2") (pintype "passive"))
      (node (ref "D2") (pin "A") (pinfunction "A_A") (pintype "passive"))
      (node (ref "TR1") (pin "15") (pinfunction "12V_DOT2_15") (pintype "passive"))
    )
    (net (code "134") (name "Net-(TR1-P2_DOT)") (class "Default")
      (node (ref "D4") (pin "A") (pinfunction "A_A") (pintype "passive"))
      (node (ref "IC1") (pin "13") (pinfunction "DRAIN_13") (pintype "output"))
      (node (ref "IC1") (pin "14") (pinfunction "DRAIN_14") (pintype "output"))
      (node (ref "IC1") (pin "15") (pinfunction "DRAIN_15") (pintype "output"))
      (node (ref "IC1") (pin "16") (pinfunction "DRAIN_16") (pintype "output"))
      (node (ref "TR1") (pin "4") (pinfunction "P2_DOT_4") (pintype "passive"))
    )
    (net (code "135") (name "Net-(TR2-P_DOT)") (class "Default")
      (node (ref "Q2") (pin "D") (pinfunction "D_D") (pintype "passive"))
      (node (ref "TR2") (pin "8") (pinfunction "P_DOT_8") (pintype "passive"))
    )
    (net (code "136") (name "Net-(X2C-1)") (class "Default")
      (node (ref "C13") (pin "2") (pinfunction "2_2") (pintype "passive"))
      (node (ref "L4") (pin "2") (pinfunction "2_2") (pintype "passive"))
      (node (ref "R7") (pin "2") (pinfunction "2_2") (pintype "passive"))
      (node (ref "X2") (pin "3") (pinfunction "1_3") (pintype "passive"))
    )
    (net (code "137") (name "Net-(X2E-1)") (class "Default")
      (node (ref "JP9") (pin "NC") (pinfunction "NC_NC") (pintype "passive"))
      (node (ref "X2") (pin "5") (pinfunction "1_5") (pintype "passive"))
    )
    (net (code "138") (name "Net-(X2F-1)") (class "Default")
      (node (ref "D26") (pin "A") (pinfunction "A_A") (pintype "passive"))
      (node (ref "X2") (pin "6") (pinfunction "1_6") (pintype "passive"))
    )
    (net (code "139") (name "PE") (class "Default")
      (node (ref "C4") (pin "1") (pinfunction "1_1") (pintype "passive"))
      (node (ref "C68") (pin "2") (pinfunction "2_2") (pintype "passive"))
      (node (ref "C69") (pin "2") (pinfunction "2_2") (pintype "passive"))
      (node (ref "C70") (pin "2") (pinfunction "2_2") (pintype "passive"))
      (node (ref "C8") (pin "1") (pinfunction "1_1") (pintype "passive"))
      (node (ref "JP2") (pin "1") (pinfunction "1_1") (pintype "passive"))
      (node (ref "JP5") (pin "NO") (pinfunction "NO_NO") (pintype "passive"))
      (node (ref "X1") (pin "3") (pinfunction "1_3") (pintype "passive"))
    )
    (net (code "140") (name "POUT+") (class "Default")
      (node (ref "C58") (pin "+") (pinfunction "+_+") (pintype "passive"))
      (node (ref "C59") (pin "1") (pinfunction "1_1") (pintype "passive"))
      (node (ref "C68") (pin "1") (pinfunction "1_1") (pintype "passive"))
      (node (ref "L9") (pin "1") (pinfunction "1_1") (pintype "passive"))
      (node (ref "R66") (pin "1") (pinfunction "1_1") (pintype "passive"))
      (node (ref "SH4") (pin "P$2") (pinfunction "GND_B_P$2") (pintype "bidirectional"))
    )
    (net (code "141") (name "PREG_OUT+") (class "Default")
      (node (ref "C61") (pin "+") (pinfunction "+_+") (pintype "passive"))
      (node (ref "C62") (pin "1") (pinfunction "1_1") (pintype "passive"))
      (node (ref "C63") (pin "1") (pinfunction "1_1") (pintype "passive"))
      (node (ref "C69") (pin "1") (pinfunction "1_1") (pintype "passive"))
      (node (ref "JP4") (pin "1") (pinfunction "1_1") (pintype "passive"))
      (node (ref "JP6") (pin "NO") (pinfunction "NO_NO") (pintype "passive"))
      (node (ref "L9") (pin "2") (pinfunction "2_2") (pintype "passive"))
      (node (ref "R66") (pin "2") (pinfunction "2_2") (pintype "passive"))
      (node (ref "R68") (pin "2") (pinfunction "2_2") (pintype "passive"))
      (node (ref "R70") (pin "2") (pinfunction "2_2") (pintype "passive"))
      (node (ref "R80") (pin "2") (pinfunction "2_2") (pintype "passive"))
      (node (ref "TP5") (pin "TIP") (pinfunction "TIP_TIP") (pintype "bidirectional"))
      (node (ref "X4") (pin "1") (pinfunction "1_1") (pintype "passive"))
      (node (ref "ZD6") (pin "C") (pinfunction "C_C") (pintype "passive"))
    )
    (net (code "142") (name "PULL") (class "Default")
      (node (ref "D22") (pin "A") (pinfunction "A_A") (pintype "passive"))
      (node (ref "IC3") (pin "9") (pinfunction "PULL_9") (pintype "output"))
      (node (ref "R53") (pin "2") (pinfunction "2_2") (pintype "passive"))
    )
    (net (code "143") (name "PUSH") (class "Default")
      (node (ref "D20") (pin "A") (pinfunction "A_A") (pintype "passive"))
      (node (ref "IC3") (pin "8") (pinfunction "PUSH_8") (pintype "output"))
      (node (ref "R47") (pin "2") (pinfunction "2_2") (pintype "passive"))
    )
    (net (code "144") (name "REF") (class "Default")
      (node (ref "C37") (pin "2") (pinfunction "2_2") (pintype "passive"))
      (node (ref "IC2") (pin "3") (pinfunction "VDDI_3") (pintype "power_in"))
      (node (ref "IC2") (pin "8") (pinfunction "VDDI_8") (pintype "power_in"))
      (node (ref "R31") (pin "2") (pinfunction "2_2") (pintype "passive"))
    )
    (net (code "145") (name "S1_DOT_OUT") (class "Default")
      (node (ref "Q8") (pin "2") (pinfunction "D_2") (pintype "passive"))
      (node (ref "R75") (pin "1") (pinfunction "1_1") (pintype "passive"))
      (node (ref "R76") (pin "1") (pinfunction "1_1") (pintype "passive"))
      (node (ref "TR3") (pin "S1_DOT") (pinfunction "S1_DOT_S1_DOT") (pintype "passive"))
    )
    (net (code "146") (name "S2_OUT") (class "Default")
      (node (ref "Q7") (pin "2") (pinfunction "D_2") (pintype "passive"))
      (node (ref "R67") (pin "1") (pinfunction "1_1") (pintype "passive"))
      (node (ref "R69") (pin "2") (pinfunction "2_2") (pintype "passive"))
      (node (ref "TR3") (pin "S2") (pinfunction "S2_S2") (pintype "passive"))
    )
    (net (code "147") (name "S_COMM") (class "Default")
      (node (ref "JP6") (pin "NC") (pinfunction "NC_NC") (pintype "passive"))
      (node (ref "SH4") (pin "P$1") (pinfunction "GND_A_P$1") (pintype "bidirectional"))
      (node (ref "TR3") (pin "S1") (pinfunction "S1_S1") (pintype "passive"))
      (node (ref "TR3") (pin "S2_DOT") (pinfunction "S2_DOT_S2_DOT") (pintype "passive"))
    )
    (net (code "148") (name "V+") (class "Default")
      (node (ref "C25") (pin "1") (pinfunction "1_1") (pintype "passive"))
      (node (ref "JP7") (pin "1") (pinfunction "1_1") (pintype "passive"))
      (node (ref "L6") (pin "2") (pinfunction "2_2") (pintype "passive"))
      (node (ref "R21") (pin "2") (pinfunction "2_2") (pintype "passive"))
      (node (ref "R78") (pin "1") (pinfunction "1_1") (pintype "passive"))
      (node (ref "R79") (pin "1") (pinfunction "1_1") (pintype "passive"))
      (node (ref "X2") (pin "7") (pinfunction "1_7") (pintype "passive"))
    )
    (net (code "149") (name "V-") (class "Default")
      (node (ref "C19") (pin "2") (pinfunction "2_2") (pintype "passive"))
      (node (ref "JP8") (pin "2") (pinfunction "2_2") (pintype "passive"))
      (node (ref "L5") (pin "2") (pinfunction "2_2") (pintype "passive"))
      (node (ref "X2") (pin "9") (pinfunction "1_9") (pintype "passive"))
    )
    (net (code "150") (name "~{FAULT}") (class "Default")
      (node (ref "D26") (pin "C") (pinfunction "C_C") (pintype "passive"))
      (node (ref "LED1") (pin "BC") (pinfunction "C_BC") (pintype "passive"))
      (node (ref "OK2") (pin "4") (pinfunction "COL_4") (pintype "passive"))
    )
  )
)
